# cc2_schematic.net
KiCad netlist of a schematic drawn in EasyEDA
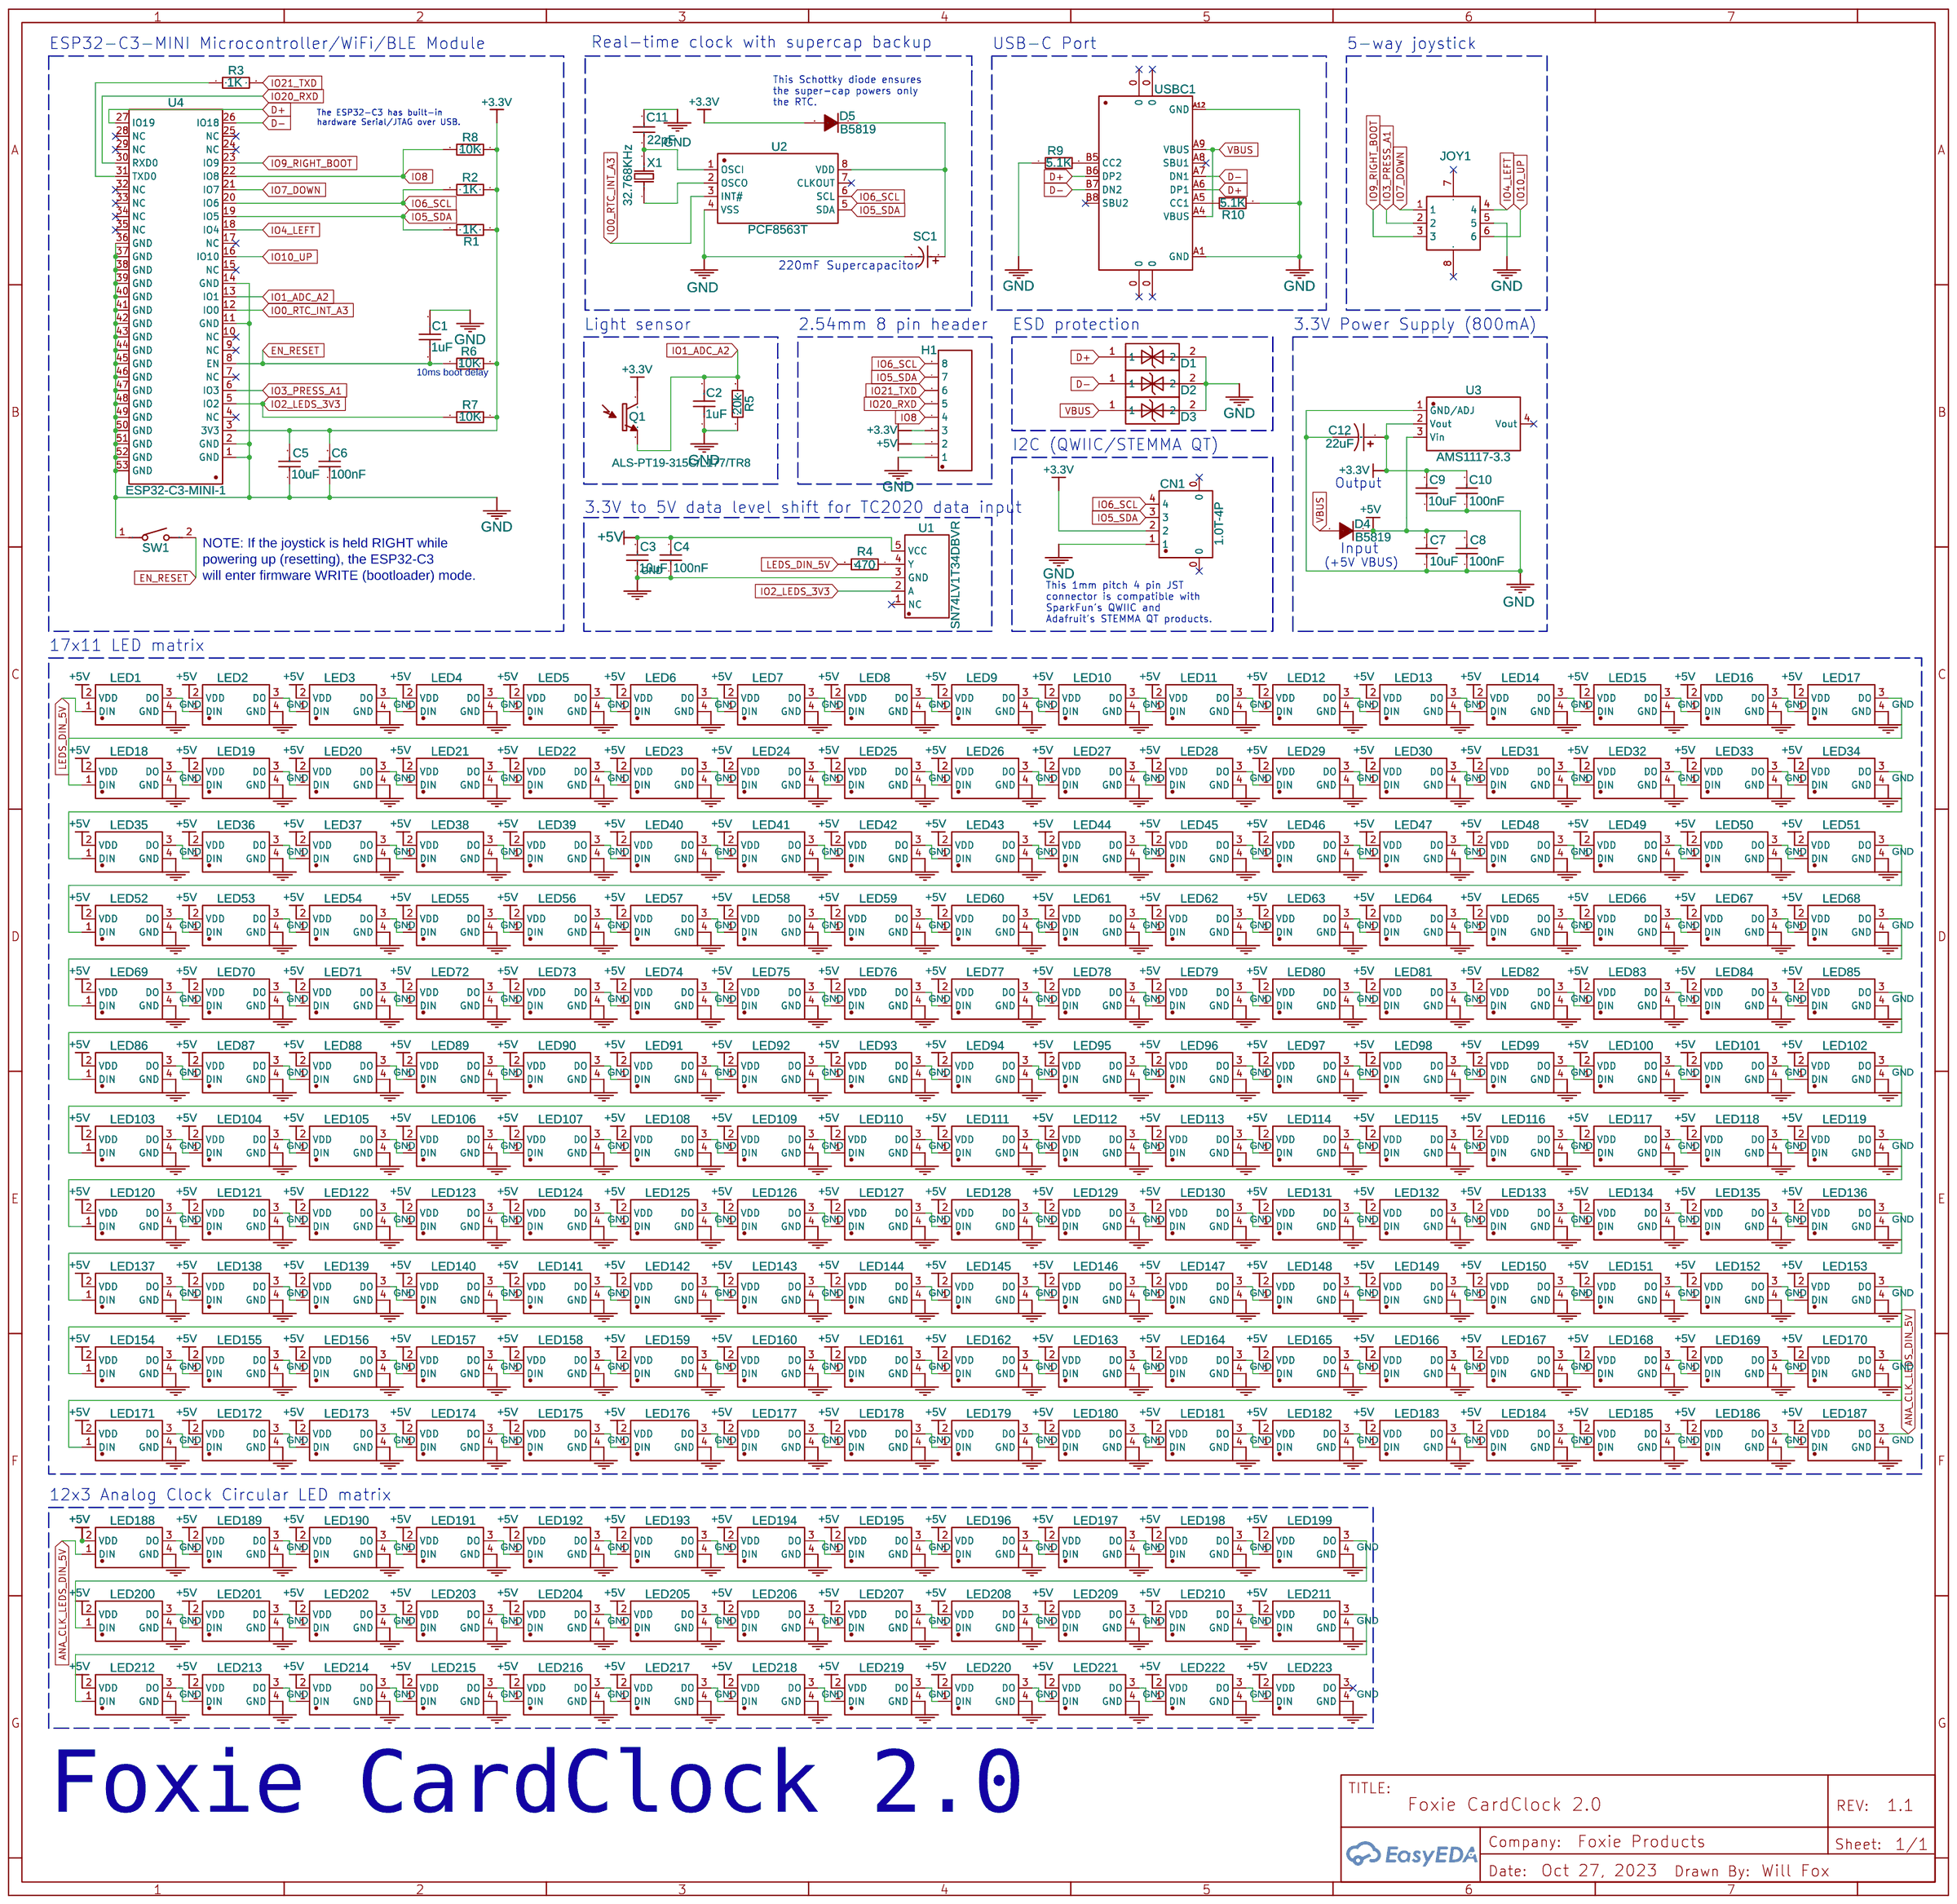
[diagram p0: schematic sheet]

(export (version "E")
  (design (tool "Eeschema 10.0.6"))
  (components
    (comp (ref "C1")
      (value "1uF")
      (fields (field (name "Manufacturer Part") "CL05A105KA5NQNC") (field (name "Manufacturer") "SAMSUNG"))
      (libsource (lib "") (part "CL05A105KA5NQNC"))
    )
    (comp (ref "C2")
      (value "1uF")
      (fields (field (name "Manufacturer Part") "CL05A105KA5NQNC") (field (name "Manufacturer") "SAMSUNG"))
      (libsource (lib "") (part "CL05A105KA5NQNC"))
    )
    (comp (ref "C3")
      (value "10uF")
      (fields (field (name "Manufacturer Part") "CL05A106MQ5NUNC") (field (name "Manufacturer") "SAMSUNG"))
      (libsource (lib "") (part "CL05A106MQ5NUNC"))
    )
    (comp (ref "C4")
      (value "100nF")
      (fields (field (name "Manufacturer Part") "CL05B104KO5NNNC") (field (name "Manufacturer") "SAMSUNG"))
      (libsource (lib "") (part "CL05B104KO5NNNC"))
    )
    (comp (ref "C5")
      (value "10uF")
      (fields (field (name "Manufacturer Part") "CL05A106MQ5NUNC") (field (name "Manufacturer") "SAMSUNG"))
      (libsource (lib "") (part "CL05A106MQ5NUNC"))
    )
    (comp (ref "C6")
      (value "100nF")
      (fields (field (name "Manufacturer Part") "CL05B104KO5NNNC") (field (name "Manufacturer") "SAMSUNG"))
      (libsource (lib "") (part "CL05B104KO5NNNC"))
    )
    (comp (ref "C7")
      (value "10uF")
      (fields (field (name "Manufacturer Part") "CL05A106MQ5NUNC") (field (name "Manufacturer") "SAMSUNG"))
      (libsource (lib "") (part "CL05A106MQ5NUNC"))
    )
    (comp (ref "C8")
      (value "100nF")
      (fields (field (name "Manufacturer Part") "CL05B104KO5NNNC") (field (name "Manufacturer") "SAMSUNG"))
      (libsource (lib "") (part "CL05B104KO5NNNC"))
    )
    (comp (ref "C9")
      (value "10uF")
      (fields (field (name "Manufacturer Part") "CL05A106MQ5NUNC") (field (name "Manufacturer") "SAMSUNG"))
      (libsource (lib "") (part "CL05A106MQ5NUNC"))
    )
    (comp (ref "C10")
      (value "100nF")
      (fields (field (name "Manufacturer Part") "CL05B104KO5NNNC") (field (name "Manufacturer") "SAMSUNG"))
      (libsource (lib "") (part "CL05B104KO5NNNC"))
    )
    (comp (ref "C11")
      (value "22pF")
      (fields (field (name "Manufacturer Part") "0402CG220J500NT") (field (name "Manufacturer") "FH"))
      (libsource (lib "") (part "0402CG220J500NT"))
    )
    (comp (ref "C12")
      (value "22uF")
      (fields (field (name "Manufacturer Part") "TC212A226K010Y") (field (name "Manufacturer") "Sunlord"))
      (libsource (lib "") (part "TC212A226K010Y"))
    )
    (comp (ref "CN1")
      (value "1.0T-4P")
      (fields (field (name "Manufacturer") "Boom Precision Elec"))
      (libsource (lib "") (part "1.0T-4P_C145956"))
    )
    (comp (ref "D1")
      (value "ULCE1005A015FR")
      (fields (field (name "Manufacturer") "ICT"))
      (libsource (lib "") (part "ULCE1005A015FR"))
    )
    (comp (ref "D2")
      (value "ULCE1005A015FR")
      (fields (field (name "Manufacturer") "ICT"))
      (libsource (lib "") (part "ULCE1005A015FR"))
    )
    (comp (ref "D3")
      (value "ULCE1005A015FR")
      (fields (field (name "Manufacturer") "ICT"))
      (libsource (lib "") (part "ULCE1005A015FR"))
    )
    (comp (ref "D4")
      (value "B5819")
      (fields (field (name "Manufacturer Part") "B5819W") (field (name "Manufacturer") "CJ"))
      (libsource (lib "") (part "B5819W_C8598"))
    )
    (comp (ref "D5")
      (value "B5819")
      (fields (field (name "Manufacturer Part") "B5819W") (field (name "Manufacturer") "CJ"))
      (libsource (lib "") (part "B5819W_C8598"))
    )
    (comp (ref "H1")
      (value "Header-Male-2.54_1x8")
      (fields
        (field (name "Manufacturer Part") "210S-1*8P L=11.6MMGold-plated black")
        (field (name "Manufacturer") "Ckmtw")
      )
      (libsource (lib "") (part "Header-Male-2.54_1x8"))
    )
    (comp (ref "JOY1")
      (value "K1-5202UA-02")
      (fields (field (name "Manufacturer") "HRO"))
      (libsource (lib "") (part "K1-5202UA-02"))
    )
    (comp (ref "LED1")
      (value "TC2020RGB-3CJH-TX1812Z5")
      (fields (field (name "Manufacturer") "TCWIN"))
      (libsource (lib "") (part "TC2020RGB-3CJH-TX1812Z5"))
    )
    (comp (ref "LED2")
      (value "TC2020RGB-3CJH-TX1812Z5")
      (fields (field (name "Manufacturer") "TCWIN"))
      (libsource (lib "") (part "TC2020RGB-3CJH-TX1812Z5"))
    )
    (comp (ref "LED3")
      (value "TC2020RGB-3CJH-TX1812Z5")
      (fields (field (name "Manufacturer") "TCWIN"))
      (libsource (lib "") (part "TC2020RGB-3CJH-TX1812Z5"))
    )
    (comp (ref "LED4")
      (value "TC2020RGB-3CJH-TX1812Z5")
      (fields (field (name "Manufacturer") "TCWIN"))
      (libsource (lib "") (part "TC2020RGB-3CJH-TX1812Z5"))
    )
    (comp (ref "LED5")
      (value "TC2020RGB-3CJH-TX1812Z5")
      (fields (field (name "Manufacturer") "TCWIN"))
      (libsource (lib "") (part "TC2020RGB-3CJH-TX1812Z5"))
    )
    (comp (ref "LED6")
      (value "TC2020RGB-3CJH-TX1812Z5")
      (fields (field (name "Manufacturer") "TCWIN"))
      (libsource (lib "") (part "TC2020RGB-3CJH-TX1812Z5"))
    )
    (comp (ref "LED7")
      (value "TC2020RGB-3CJH-TX1812Z5")
      (fields (field (name "Manufacturer") "TCWIN"))
      (libsource (lib "") (part "TC2020RGB-3CJH-TX1812Z5"))
    )
    (comp (ref "LED8")
      (value "TC2020RGB-3CJH-TX1812Z5")
      (fields (field (name "Manufacturer") "TCWIN"))
      (libsource (lib "") (part "TC2020RGB-3CJH-TX1812Z5"))
    )
    (comp (ref "LED9")
      (value "TC2020RGB-3CJH-TX1812Z5")
      (fields (field (name "Manufacturer") "TCWIN"))
      (libsource (lib "") (part "TC2020RGB-3CJH-TX1812Z5"))
    )
    (comp (ref "LED10")
      (value "TC2020RGB-3CJH-TX1812Z5")
      (fields (field (name "Manufacturer") "TCWIN"))
      (libsource (lib "") (part "TC2020RGB-3CJH-TX1812Z5"))
    )
    (comp (ref "LED11")
      (value "TC2020RGB-3CJH-TX1812Z5")
      (fields (field (name "Manufacturer") "TCWIN"))
      (libsource (lib "") (part "TC2020RGB-3CJH-TX1812Z5"))
    )
    (comp (ref "LED12")
      (value "TC2020RGB-3CJH-TX1812Z5")
      (fields (field (name "Manufacturer") "TCWIN"))
      (libsource (lib "") (part "TC2020RGB-3CJH-TX1812Z5"))
    )
    (comp (ref "LED13")
      (value "TC2020RGB-3CJH-TX1812Z5")
      (fields (field (name "Manufacturer") "TCWIN"))
      (libsource (lib "") (part "TC2020RGB-3CJH-TX1812Z5"))
    )
    (comp (ref "LED14")
      (value "TC2020RGB-3CJH-TX1812Z5")
      (fields (field (name "Manufacturer") "TCWIN"))
      (libsource (lib "") (part "TC2020RGB-3CJH-TX1812Z5"))
    )
    (comp (ref "LED15")
      (value "TC2020RGB-3CJH-TX1812Z5")
      (fields (field (name "Manufacturer") "TCWIN"))
      (libsource (lib "") (part "TC2020RGB-3CJH-TX1812Z5"))
    )
    (comp (ref "LED16")
      (value "TC2020RGB-3CJH-TX1812Z5")
      (fields (field (name "Manufacturer") "TCWIN"))
      (libsource (lib "") (part "TC2020RGB-3CJH-TX1812Z5"))
    )
    (comp (ref "LED17")
      (value "TC2020RGB-3CJH-TX1812Z5")
      (fields (field (name "Manufacturer") "TCWIN"))
      (libsource (lib "") (part "TC2020RGB-3CJH-TX1812Z5"))
    )
    (comp (ref "LED18")
      (value "TC2020RGB-3CJH-TX1812Z5")
      (fields (field (name "Manufacturer") "TCWIN"))
      (libsource (lib "") (part "TC2020RGB-3CJH-TX1812Z5"))
    )
    (comp (ref "LED19")
      (value "TC2020RGB-3CJH-TX1812Z5")
      (fields (field (name "Manufacturer") "TCWIN"))
      (libsource (lib "") (part "TC2020RGB-3CJH-TX1812Z5"))
    )
    (comp (ref "LED20")
      (value "TC2020RGB-3CJH-TX1812Z5")
      (fields (field (name "Manufacturer") "TCWIN"))
      (libsource (lib "") (part "TC2020RGB-3CJH-TX1812Z5"))
    )
    (comp (ref "LED21")
      (value "TC2020RGB-3CJH-TX1812Z5")
      (fields (field (name "Manufacturer") "TCWIN"))
      (libsource (lib "") (part "TC2020RGB-3CJH-TX1812Z5"))
    )
    (comp (ref "LED22")
      (value "TC2020RGB-3CJH-TX1812Z5")
      (fields (field (name "Manufacturer") "TCWIN"))
      (libsource (lib "") (part "TC2020RGB-3CJH-TX1812Z5"))
    )
    (comp (ref "LED23")
      (value "TC2020RGB-3CJH-TX1812Z5")
      (fields (field (name "Manufacturer") "TCWIN"))
      (libsource (lib "") (part "TC2020RGB-3CJH-TX1812Z5"))
    )
    (comp (ref "LED24")
      (value "TC2020RGB-3CJH-TX1812Z5")
      (fields (field (name "Manufacturer") "TCWIN"))
      (libsource (lib "") (part "TC2020RGB-3CJH-TX1812Z5"))
    )
    (comp (ref "LED25")
      (value "TC2020RGB-3CJH-TX1812Z5")
      (fields (field (name "Manufacturer") "TCWIN"))
      (libsource (lib "") (part "TC2020RGB-3CJH-TX1812Z5"))
    )
    (comp (ref "LED26")
      (value "TC2020RGB-3CJH-TX1812Z5")
      (fields (field (name "Manufacturer") "TCWIN"))
      (libsource (lib "") (part "TC2020RGB-3CJH-TX1812Z5"))
    )
    (comp (ref "LED27")
      (value "TC2020RGB-3CJH-TX1812Z5")
      (fields (field (name "Manufacturer") "TCWIN"))
      (libsource (lib "") (part "TC2020RGB-3CJH-TX1812Z5"))
    )
    (comp (ref "LED28")
      (value "TC2020RGB-3CJH-TX1812Z5")
      (fields (field (name "Manufacturer") "TCWIN"))
      (libsource (lib "") (part "TC2020RGB-3CJH-TX1812Z5"))
    )
    (comp (ref "LED29")
      (value "TC2020RGB-3CJH-TX1812Z5")
      (fields (field (name "Manufacturer") "TCWIN"))
      (libsource (lib "") (part "TC2020RGB-3CJH-TX1812Z5"))
    )
    (comp (ref "LED30")
      (value "TC2020RGB-3CJH-TX1812Z5")
      (fields (field (name "Manufacturer") "TCWIN"))
      (libsource (lib "") (part "TC2020RGB-3CJH-TX1812Z5"))
    )
    (comp (ref "LED31")
      (value "TC2020RGB-3CJH-TX1812Z5")
      (fields (field (name "Manufacturer") "TCWIN"))
      (libsource (lib "") (part "TC2020RGB-3CJH-TX1812Z5"))
    )
    (comp (ref "LED32")
      (value "TC2020RGB-3CJH-TX1812Z5")
      (fields (field (name "Manufacturer") "TCWIN"))
      (libsource (lib "") (part "TC2020RGB-3CJH-TX1812Z5"))
    )
    (comp (ref "LED33")
      (value "TC2020RGB-3CJH-TX1812Z5")
      (fields (field (name "Manufacturer") "TCWIN"))
      (libsource (lib "") (part "TC2020RGB-3CJH-TX1812Z5"))
    )
    (comp (ref "LED34")
      (value "TC2020RGB-3CJH-TX1812Z5")
      (fields (field (name "Manufacturer") "TCWIN"))
      (libsource (lib "") (part "TC2020RGB-3CJH-TX1812Z5"))
    )
    (comp (ref "LED35")
      (value "TC2020RGB-3CJH-TX1812Z5")
      (fields (field (name "Manufacturer") "TCWIN"))
      (libsource (lib "") (part "TC2020RGB-3CJH-TX1812Z5"))
    )
    (comp (ref "LED36")
      (value "TC2020RGB-3CJH-TX1812Z5")
      (fields (field (name "Manufacturer") "TCWIN"))
      (libsource (lib "") (part "TC2020RGB-3CJH-TX1812Z5"))
    )
    (comp (ref "LED37")
      (value "TC2020RGB-3CJH-TX1812Z5")
      (fields (field (name "Manufacturer") "TCWIN"))
      (libsource (lib "") (part "TC2020RGB-3CJH-TX1812Z5"))
    )
    (comp (ref "LED38")
      (value "TC2020RGB-3CJH-TX1812Z5")
      (fields (field (name "Manufacturer") "TCWIN"))
      (libsource (lib "") (part "TC2020RGB-3CJH-TX1812Z5"))
    )
    (comp (ref "LED39")
      (value "TC2020RGB-3CJH-TX1812Z5")
      (fields (field (name "Manufacturer") "TCWIN"))
      (libsource (lib "") (part "TC2020RGB-3CJH-TX1812Z5"))
    )
    (comp (ref "LED40")
      (value "TC2020RGB-3CJH-TX1812Z5")
      (fields (field (name "Manufacturer") "TCWIN"))
      (libsource (lib "") (part "TC2020RGB-3CJH-TX1812Z5"))
    )
    (comp (ref "LED41")
      (value "TC2020RGB-3CJH-TX1812Z5")
      (fields (field (name "Manufacturer") "TCWIN"))
      (libsource (lib "") (part "TC2020RGB-3CJH-TX1812Z5"))
    )
    (comp (ref "LED42")
      (value "TC2020RGB-3CJH-TX1812Z5")
      (fields (field (name "Manufacturer") "TCWIN"))
      (libsource (lib "") (part "TC2020RGB-3CJH-TX1812Z5"))
    )
    (comp (ref "LED43")
      (value "TC2020RGB-3CJH-TX1812Z5")
      (fields (field (name "Manufacturer") "TCWIN"))
      (libsource (lib "") (part "TC2020RGB-3CJH-TX1812Z5"))
    )
    (comp (ref "LED44")
      (value "TC2020RGB-3CJH-TX1812Z5")
      (fields (field (name "Manufacturer") "TCWIN"))
      (libsource (lib "") (part "TC2020RGB-3CJH-TX1812Z5"))
    )
    (comp (ref "LED45")
      (value "TC2020RGB-3CJH-TX1812Z5")
      (fields (field (name "Manufacturer") "TCWIN"))
      (libsource (lib "") (part "TC2020RGB-3CJH-TX1812Z5"))
    )
    (comp (ref "LED46")
      (value "TC2020RGB-3CJH-TX1812Z5")
      (fields (field (name "Manufacturer") "TCWIN"))
      (libsource (lib "") (part "TC2020RGB-3CJH-TX1812Z5"))
    )
    (comp (ref "LED47")
      (value "TC2020RGB-3CJH-TX1812Z5")
      (fields (field (name "Manufacturer") "TCWIN"))
      (libsource (lib "") (part "TC2020RGB-3CJH-TX1812Z5"))
    )
    (comp (ref "LED48")
      (value "TC2020RGB-3CJH-TX1812Z5")
      (fields (field (name "Manufacturer") "TCWIN"))
      (libsource (lib "") (part "TC2020RGB-3CJH-TX1812Z5"))
    )
    (comp (ref "LED49")
      (value "TC2020RGB-3CJH-TX1812Z5")
      (fields (field (name "Manufacturer") "TCWIN"))
      (libsource (lib "") (part "TC2020RGB-3CJH-TX1812Z5"))
    )
    (comp (ref "LED50")
      (value "TC2020RGB-3CJH-TX1812Z5")
      (fields (field (name "Manufacturer") "TCWIN"))
      (libsource (lib "") (part "TC2020RGB-3CJH-TX1812Z5"))
    )
    (comp (ref "LED51")
      (value "TC2020RGB-3CJH-TX1812Z5")
      (fields (field (name "Manufacturer") "TCWIN"))
      (libsource (lib "") (part "TC2020RGB-3CJH-TX1812Z5"))
    )
    (comp (ref "LED52")
      (value "TC2020RGB-3CJH-TX1812Z5")
      (fields (field (name "Manufacturer") "TCWIN"))
      (libsource (lib "") (part "TC2020RGB-3CJH-TX1812Z5"))
    )
    (comp (ref "LED53")
      (value "TC2020RGB-3CJH-TX1812Z5")
      (fields (field (name "Manufacturer") "TCWIN"))
      (libsource (lib "") (part "TC2020RGB-3CJH-TX1812Z5"))
    )
    (comp (ref "LED54")
      (value "TC2020RGB-3CJH-TX1812Z5")
      (fields (field (name "Manufacturer") "TCWIN"))
      (libsource (lib "") (part "TC2020RGB-3CJH-TX1812Z5"))
    )
    (comp (ref "LED55")
      (value "TC2020RGB-3CJH-TX1812Z5")
      (fields (field (name "Manufacturer") "TCWIN"))
      (libsource (lib "") (part "TC2020RGB-3CJH-TX1812Z5"))
    )
    (comp (ref "LED56")
      (value "TC2020RGB-3CJH-TX1812Z5")
      (fields (field (name "Manufacturer") "TCWIN"))
      (libsource (lib "") (part "TC2020RGB-3CJH-TX1812Z5"))
    )
    (comp (ref "LED57")
      (value "TC2020RGB-3CJH-TX1812Z5")
      (fields (field (name "Manufacturer") "TCWIN"))
      (libsource (lib "") (part "TC2020RGB-3CJH-TX1812Z5"))
    )
    (comp (ref "LED58")
      (value "TC2020RGB-3CJH-TX1812Z5")
      (fields (field (name "Manufacturer") "TCWIN"))
      (libsource (lib "") (part "TC2020RGB-3CJH-TX1812Z5"))
    )
    (comp (ref "LED59")
      (value "TC2020RGB-3CJH-TX1812Z5")
      (fields (field (name "Manufacturer") "TCWIN"))
      (libsource (lib "") (part "TC2020RGB-3CJH-TX1812Z5"))
    )
    (comp (ref "LED60")
      (value "TC2020RGB-3CJH-TX1812Z5")
      (fields (field (name "Manufacturer") "TCWIN"))
      (libsource (lib "") (part "TC2020RGB-3CJH-TX1812Z5"))
    )
    (comp (ref "LED61")
      (value "TC2020RGB-3CJH-TX1812Z5")
      (fields (field (name "Manufacturer") "TCWIN"))
      (libsource (lib "") (part "TC2020RGB-3CJH-TX1812Z5"))
    )
    (comp (ref "LED62")
      (value "TC2020RGB-3CJH-TX1812Z5")
      (fields (field (name "Manufacturer") "TCWIN"))
      (libsource (lib "") (part "TC2020RGB-3CJH-TX1812Z5"))
    )
    (comp (ref "LED63")
      (value "TC2020RGB-3CJH-TX1812Z5")
      (fields (field (name "Manufacturer") "TCWIN"))
      (libsource (lib "") (part "TC2020RGB-3CJH-TX1812Z5"))
    )
    (comp (ref "LED64")
      (value "TC2020RGB-3CJH-TX1812Z5")
      (fields (field (name "Manufacturer") "TCWIN"))
      (libsource (lib "") (part "TC2020RGB-3CJH-TX1812Z5"))
    )
    (comp (ref "LED65")
      (value "TC2020RGB-3CJH-TX1812Z5")
      (fields (field (name "Manufacturer") "TCWIN"))
      (libsource (lib "") (part "TC2020RGB-3CJH-TX1812Z5"))
    )
    (comp (ref "LED66")
      (value "TC2020RGB-3CJH-TX1812Z5")
      (fields (field (name "Manufacturer") "TCWIN"))
      (libsource (lib "") (part "TC2020RGB-3CJH-TX1812Z5"))
    )
    (comp (ref "LED67")
      (value "TC2020RGB-3CJH-TX1812Z5")
      (fields (field (name "Manufacturer") "TCWIN"))
      (libsource (lib "") (part "TC2020RGB-3CJH-TX1812Z5"))
    )
    (comp (ref "LED68")
      (value "TC2020RGB-3CJH-TX1812Z5")
      (fields (field (name "Manufacturer") "TCWIN"))
      (libsource (lib "") (part "TC2020RGB-3CJH-TX1812Z5"))
    )
    (comp (ref "LED69")
      (value "TC2020RGB-3CJH-TX1812Z5")
      (fields (field (name "Manufacturer") "TCWIN"))
      (libsource (lib "") (part "TC2020RGB-3CJH-TX1812Z5"))
    )
    (comp (ref "LED70")
      (value "TC2020RGB-3CJH-TX1812Z5")
      (fields (field (name "Manufacturer") "TCWIN"))
      (libsource (lib "") (part "TC2020RGB-3CJH-TX1812Z5"))
    )
    (comp (ref "LED71")
      (value "TC2020RGB-3CJH-TX1812Z5")
      (fields (field (name "Manufacturer") "TCWIN"))
      (libsource (lib "") (part "TC2020RGB-3CJH-TX1812Z5"))
    )
    (comp (ref "LED72")
      (value "TC2020RGB-3CJH-TX1812Z5")
      (fields (field (name "Manufacturer") "TCWIN"))
      (libsource (lib "") (part "TC2020RGB-3CJH-TX1812Z5"))
    )
    (comp (ref "LED73")
      (value "TC2020RGB-3CJH-TX1812Z5")
      (fields (field (name "Manufacturer") "TCWIN"))
      (libsource (lib "") (part "TC2020RGB-3CJH-TX1812Z5"))
    )
    (comp (ref "LED74")
      (value "TC2020RGB-3CJH-TX1812Z5")
      (fields (field (name "Manufacturer") "TCWIN"))
      (libsource (lib "") (part "TC2020RGB-3CJH-TX1812Z5"))
    )
    (comp (ref "LED75")
      (value "TC2020RGB-3CJH-TX1812Z5")
      (fields (field (name "Manufacturer") "TCWIN"))
      (libsource (lib "") (part "TC2020RGB-3CJH-TX1812Z5"))
    )
    (comp (ref "LED76")
      (value "TC2020RGB-3CJH-TX1812Z5")
      (fields (field (name "Manufacturer") "TCWIN"))
      (libsource (lib "") (part "TC2020RGB-3CJH-TX1812Z5"))
    )
    (comp (ref "LED77")
      (value "TC2020RGB-3CJH-TX1812Z5")
      (fields (field (name "Manufacturer") "TCWIN"))
      (libsource (lib "") (part "TC2020RGB-3CJH-TX1812Z5"))
    )
    (comp (ref "LED78")
      (value "TC2020RGB-3CJH-TX1812Z5")
      (fields (field (name "Manufacturer") "TCWIN"))
      (libsource (lib "") (part "TC2020RGB-3CJH-TX1812Z5"))
    )
    (comp (ref "LED79")
      (value "TC2020RGB-3CJH-TX1812Z5")
      (fields (field (name "Manufacturer") "TCWIN"))
      (libsource (lib "") (part "TC2020RGB-3CJH-TX1812Z5"))
    )
    (comp (ref "LED80")
      (value "TC2020RGB-3CJH-TX1812Z5")
      (fields (field (name "Manufacturer") "TCWIN"))
      (libsource (lib "") (part "TC2020RGB-3CJH-TX1812Z5"))
    )
    (comp (ref "LED81")
      (value "TC2020RGB-3CJH-TX1812Z5")
      (fields (field (name "Manufacturer") "TCWIN"))
      (libsource (lib "") (part "TC2020RGB-3CJH-TX1812Z5"))
    )
    (comp (ref "LED82")
      (value "TC2020RGB-3CJH-TX1812Z5")
      (fields (field (name "Manufacturer") "TCWIN"))
      (libsource (lib "") (part "TC2020RGB-3CJH-TX1812Z5"))
    )
    (comp (ref "LED83")
      (value "TC2020RGB-3CJH-TX1812Z5")
      (fields (field (name "Manufacturer") "TCWIN"))
      (libsource (lib "") (part "TC2020RGB-3CJH-TX1812Z5"))
    )
    (comp (ref "LED84")
      (value "TC2020RGB-3CJH-TX1812Z5")
      (fields (field (name "Manufacturer") "TCWIN"))
      (libsource (lib "") (part "TC2020RGB-3CJH-TX1812Z5"))
    )
    (comp (ref "LED85")
      (value "TC2020RGB-3CJH-TX1812Z5")
      (fields (field (name "Manufacturer") "TCWIN"))
      (libsource (lib "") (part "TC2020RGB-3CJH-TX1812Z5"))
    )
    (comp (ref "LED86")
      (value "TC2020RGB-3CJH-TX1812Z5")
      (fields (field (name "Manufacturer") "TCWIN"))
      (libsource (lib "") (part "TC2020RGB-3CJH-TX1812Z5"))
    )
    (comp (ref "LED87")
      (value "TC2020RGB-3CJH-TX1812Z5")
      (fields (field (name "Manufacturer") "TCWIN"))
      (libsource (lib "") (part "TC2020RGB-3CJH-TX1812Z5"))
    )
    (comp (ref "LED88")
      (value "TC2020RGB-3CJH-TX1812Z5")
      (fields (field (name "Manufacturer") "TCWIN"))
      (libsource (lib "") (part "TC2020RGB-3CJH-TX1812Z5"))
    )
    (comp (ref "LED89")
      (value "TC2020RGB-3CJH-TX1812Z5")
      (fields (field (name "Manufacturer") "TCWIN"))
      (libsource (lib "") (part "TC2020RGB-3CJH-TX1812Z5"))
    )
    (comp (ref "LED90")
      (value "TC2020RGB-3CJH-TX1812Z5")
      (fields (field (name "Manufacturer") "TCWIN"))
      (libsource (lib "") (part "TC2020RGB-3CJH-TX1812Z5"))
    )
    (comp (ref "LED91")
      (value "TC2020RGB-3CJH-TX1812Z5")
      (fields (field (name "Manufacturer") "TCWIN"))
      (libsource (lib "") (part "TC2020RGB-3CJH-TX1812Z5"))
    )
    (comp (ref "LED92")
      (value "TC2020RGB-3CJH-TX1812Z5")
      (fields (field (name "Manufacturer") "TCWIN"))
      (libsource (lib "") (part "TC2020RGB-3CJH-TX1812Z5"))
    )
    (comp (ref "LED93")
      (value "TC2020RGB-3CJH-TX1812Z5")
      (fields (field (name "Manufacturer") "TCWIN"))
      (libsource (lib "") (part "TC2020RGB-3CJH-TX1812Z5"))
    )
    (comp (ref "LED94")
      (value "TC2020RGB-3CJH-TX1812Z5")
      (fields (field (name "Manufacturer") "TCWIN"))
      (libsource (lib "") (part "TC2020RGB-3CJH-TX1812Z5"))
    )
    (comp (ref "LED95")
      (value "TC2020RGB-3CJH-TX1812Z5")
      (fields (field (name "Manufacturer") "TCWIN"))
      (libsource (lib "") (part "TC2020RGB-3CJH-TX1812Z5"))
    )
    (comp (ref "LED96")
      (value "TC2020RGB-3CJH-TX1812Z5")
      (fields (field (name "Manufacturer") "TCWIN"))
      (libsource (lib "") (part "TC2020RGB-3CJH-TX1812Z5"))
    )
    (comp (ref "LED97")
      (value "TC2020RGB-3CJH-TX1812Z5")
      (fields (field (name "Manufacturer") "TCWIN"))
      (libsource (lib "") (part "TC2020RGB-3CJH-TX1812Z5"))
    )
    (comp (ref "LED98")
      (value "TC2020RGB-3CJH-TX1812Z5")
      (fields (field (name "Manufacturer") "TCWIN"))
      (libsource (lib "") (part "TC2020RGB-3CJH-TX1812Z5"))
    )
    (comp (ref "LED99")
      (value "TC2020RGB-3CJH-TX1812Z5")
      (fields (field (name "Manufacturer") "TCWIN"))
      (libsource (lib "") (part "TC2020RGB-3CJH-TX1812Z5"))
    )
    (comp (ref "LED100")
      (value "TC2020RGB-3CJH-TX1812Z5")
      (fields (field (name "Manufacturer") "TCWIN"))
      (libsource (lib "") (part "TC2020RGB-3CJH-TX1812Z5"))
    )
    (comp (ref "LED101")
      (value "TC2020RGB-3CJH-TX1812Z5")
      (fields (field (name "Manufacturer") "TCWIN"))
      (libsource (lib "") (part "TC2020RGB-3CJH-TX1812Z5"))
    )
    (comp (ref "LED102")
      (value "TC2020RGB-3CJH-TX1812Z5")
      (fields (field (name "Manufacturer") "TCWIN"))
      (libsource (lib "") (part "TC2020RGB-3CJH-TX1812Z5"))
    )
    (comp (ref "LED103")
      (value "TC2020RGB-3CJH-TX1812Z5")
      (fields (field (name "Manufacturer") "TCWIN"))
      (libsource (lib "") (part "TC2020RGB-3CJH-TX1812Z5"))
    )
    (comp (ref "LED104")
      (value "TC2020RGB-3CJH-TX1812Z5")
      (fields (field (name "Manufacturer") "TCWIN"))
      (libsource (lib "") (part "TC2020RGB-3CJH-TX1812Z5"))
    )
    (comp (ref "LED105")
      (value "TC2020RGB-3CJH-TX1812Z5")
      (fields (field (name "Manufacturer") "TCWIN"))
      (libsource (lib "") (part "TC2020RGB-3CJH-TX1812Z5"))
    )
    (comp (ref "LED106")
      (value "TC2020RGB-3CJH-TX1812Z5")
      (fields (field (name "Manufacturer") "TCWIN"))
      (libsource (lib "") (part "TC2020RGB-3CJH-TX1812Z5"))
    )
    (comp (ref "LED107")
      (value "TC2020RGB-3CJH-TX1812Z5")
      (fields (field (name "Manufacturer") "TCWIN"))
      (libsource (lib "") (part "TC2020RGB-3CJH-TX1812Z5"))
    )
    (comp (ref "LED108")
      (value "TC2020RGB-3CJH-TX1812Z5")
      (fields (field (name "Manufacturer") "TCWIN"))
      (libsource (lib "") (part "TC2020RGB-3CJH-TX1812Z5"))
    )
    (comp (ref "LED109")
      (value "TC2020RGB-3CJH-TX1812Z5")
      (fields (field (name "Manufacturer") "TCWIN"))
      (libsource (lib "") (part "TC2020RGB-3CJH-TX1812Z5"))
    )
    (comp (ref "LED110")
      (value "TC2020RGB-3CJH-TX1812Z5")
      (fields (field (name "Manufacturer") "TCWIN"))
      (libsource (lib "") (part "TC2020RGB-3CJH-TX1812Z5"))
    )
    (comp (ref "LED111")
      (value "TC2020RGB-3CJH-TX1812Z5")
      (fields (field (name "Manufacturer") "TCWIN"))
      (libsource (lib "") (part "TC2020RGB-3CJH-TX1812Z5"))
    )
    (comp (ref "LED112")
      (value "TC2020RGB-3CJH-TX1812Z5")
      (fields (field (name "Manufacturer") "TCWIN"))
      (libsource (lib "") (part "TC2020RGB-3CJH-TX1812Z5"))
    )
    (comp (ref "LED113")
      (value "TC2020RGB-3CJH-TX1812Z5")
      (fields (field (name "Manufacturer") "TCWIN"))
      (libsource (lib "") (part "TC2020RGB-3CJH-TX1812Z5"))
    )
    (comp (ref "LED114")
      (value "TC2020RGB-3CJH-TX1812Z5")
      (fields (field (name "Manufacturer") "TCWIN"))
      (libsource (lib "") (part "TC2020RGB-3CJH-TX1812Z5"))
    )
    (comp (ref "LED115")
      (value "TC2020RGB-3CJH-TX1812Z5")
      (fields (field (name "Manufacturer") "TCWIN"))
      (libsource (lib "") (part "TC2020RGB-3CJH-TX1812Z5"))
    )
    (comp (ref "LED116")
      (value "TC2020RGB-3CJH-TX1812Z5")
      (fields (field (name "Manufacturer") "TCWIN"))
      (libsource (lib "") (part "TC2020RGB-3CJH-TX1812Z5"))
    )
    (comp (ref "LED117")
      (value "TC2020RGB-3CJH-TX1812Z5")
      (fields (field (name "Manufacturer") "TCWIN"))
      (libsource (lib "") (part "TC2020RGB-3CJH-TX1812Z5"))
    )
    (comp (ref "LED118")
      (value "TC2020RGB-3CJH-TX1812Z5")
      (fields (field (name "Manufacturer") "TCWIN"))
      (libsource (lib "") (part "TC2020RGB-3CJH-TX1812Z5"))
    )
    (comp (ref "LED119")
      (value "TC2020RGB-3CJH-TX1812Z5")
      (fields (field (name "Manufacturer") "TCWIN"))
      (libsource (lib "") (part "TC2020RGB-3CJH-TX1812Z5"))
    )
    (comp (ref "LED120")
      (value "TC2020RGB-3CJH-TX1812Z5")
      (fields (field (name "Manufacturer") "TCWIN"))
      (libsource (lib "") (part "TC2020RGB-3CJH-TX1812Z5"))
    )
    (comp (ref "LED121")
      (value "TC2020RGB-3CJH-TX1812Z5")
      (fields (field (name "Manufacturer") "TCWIN"))
      (libsource (lib "") (part "TC2020RGB-3CJH-TX1812Z5"))
    )
    (comp (ref "LED122")
      (value "TC2020RGB-3CJH-TX1812Z5")
      (fields (field (name "Manufacturer") "TCWIN"))
      (libsource (lib "") (part "TC2020RGB-3CJH-TX1812Z5"))
    )
    (comp (ref "LED123")
      (value "TC2020RGB-3CJH-TX1812Z5")
      (fields (field (name "Manufacturer") "TCWIN"))
      (libsource (lib "") (part "TC2020RGB-3CJH-TX1812Z5"))
    )
    (comp (ref "LED124")
      (value "TC2020RGB-3CJH-TX1812Z5")
      (fields (field (name "Manufacturer") "TCWIN"))
      (libsource (lib "") (part "TC2020RGB-3CJH-TX1812Z5"))
    )
    (comp (ref "LED125")
      (value "TC2020RGB-3CJH-TX1812Z5")
      (fields (field (name "Manufacturer") "TCWIN"))
      (libsource (lib "") (part "TC2020RGB-3CJH-TX1812Z5"))
    )
    (comp (ref "LED126")
      (value "TC2020RGB-3CJH-TX1812Z5")
      (fields (field (name "Manufacturer") "TCWIN"))
      (libsource (lib "") (part "TC2020RGB-3CJH-TX1812Z5"))
    )
    (comp (ref "LED127")
      (value "TC2020RGB-3CJH-TX1812Z5")
      (fields (field (name "Manufacturer") "TCWIN"))
      (libsource (lib "") (part "TC2020RGB-3CJH-TX1812Z5"))
    )
    (comp (ref "LED128")
      (value "TC2020RGB-3CJH-TX1812Z5")
      (fields (field (name "Manufacturer") "TCWIN"))
      (libsource (lib "") (part "TC2020RGB-3CJH-TX1812Z5"))
    )
    (comp (ref "LED129")
      (value "TC2020RGB-3CJH-TX1812Z5")
      (fields (field (name "Manufacturer") "TCWIN"))
      (libsource (lib "") (part "TC2020RGB-3CJH-TX1812Z5"))
    )
    (comp (ref "LED130")
      (value "TC2020RGB-3CJH-TX1812Z5")
      (fields (field (name "Manufacturer") "TCWIN"))
      (libsource (lib "") (part "TC2020RGB-3CJH-TX1812Z5"))
    )
    (comp (ref "LED131")
      (value "TC2020RGB-3CJH-TX1812Z5")
      (fields (field (name "Manufacturer") "TCWIN"))
      (libsource (lib "") (part "TC2020RGB-3CJH-TX1812Z5"))
    )
    (comp (ref "LED132")
      (value "TC2020RGB-3CJH-TX1812Z5")
      (fields (field (name "Manufacturer") "TCWIN"))
      (libsource (lib "") (part "TC2020RGB-3CJH-TX1812Z5"))
    )
    (comp (ref "LED133")
      (value "TC2020RGB-3CJH-TX1812Z5")
      (fields (field (name "Manufacturer") "TCWIN"))
      (libsource (lib "") (part "TC2020RGB-3CJH-TX1812Z5"))
    )
    (comp (ref "LED134")
      (value "TC2020RGB-3CJH-TX1812Z5")
      (fields (field (name "Manufacturer") "TCWIN"))
      (libsource (lib "") (part "TC2020RGB-3CJH-TX1812Z5"))
    )
    (comp (ref "LED135")
      (value "TC2020RGB-3CJH-TX1812Z5")
      (fields (field (name "Manufacturer") "TCWIN"))
      (libsource (lib "") (part "TC2020RGB-3CJH-TX1812Z5"))
    )
    (comp (ref "LED136")
      (value "TC2020RGB-3CJH-TX1812Z5")
      (fields (field (name "Manufacturer") "TCWIN"))
      (libsource (lib "") (part "TC2020RGB-3CJH-TX1812Z5"))
    )
    (comp (ref "LED137")
      (value "TC2020RGB-3CJH-TX1812Z5")
      (fields (field (name "Manufacturer") "TCWIN"))
      (libsource (lib "") (part "TC2020RGB-3CJH-TX1812Z5"))
    )
    (comp (ref "LED138")
      (value "TC2020RGB-3CJH-TX1812Z5")
      (fields (field (name "Manufacturer") "TCWIN"))
      (libsource (lib "") (part "TC2020RGB-3CJH-TX1812Z5"))
    )
    (comp (ref "LED139")
      (value "TC2020RGB-3CJH-TX1812Z5")
      (fields (field (name "Manufacturer") "TCWIN"))
      (libsource (lib "") (part "TC2020RGB-3CJH-TX1812Z5"))
    )
    (comp (ref "LED140")
      (value "TC2020RGB-3CJH-TX1812Z5")
      (fields (field (name "Manufacturer") "TCWIN"))
      (libsource (lib "") (part "TC2020RGB-3CJH-TX1812Z5"))
    )
    (comp (ref "LED141")
      (value "TC2020RGB-3CJH-TX1812Z5")
      (fields (field (name "Manufacturer") "TCWIN"))
      (libsource (lib "") (part "TC2020RGB-3CJH-TX1812Z5"))
    )
    (comp (ref "LED142")
      (value "TC2020RGB-3CJH-TX1812Z5")
      (fields (field (name "Manufacturer") "TCWIN"))
      (libsource (lib "") (part "TC2020RGB-3CJH-TX1812Z5"))
    )
    (comp (ref "LED143")
      (value "TC2020RGB-3CJH-TX1812Z5")
      (fields (field (name "Manufacturer") "TCWIN"))
      (libsource (lib "") (part "TC2020RGB-3CJH-TX1812Z5"))
    )
    (comp (ref "LED144")
      (value "TC2020RGB-3CJH-TX1812Z5")
      (fields (field (name "Manufacturer") "TCWIN"))
      (libsource (lib "") (part "TC2020RGB-3CJH-TX1812Z5"))
    )
    (comp (ref "LED145")
      (value "TC2020RGB-3CJH-TX1812Z5")
      (fields (field (name "Manufacturer") "TCWIN"))
      (libsource (lib "") (part "TC2020RGB-3CJH-TX1812Z5"))
    )
    (comp (ref "LED146")
      (value "TC2020RGB-3CJH-TX1812Z5")
      (fields (field (name "Manufacturer") "TCWIN"))
      (libsource (lib "") (part "TC2020RGB-3CJH-TX1812Z5"))
    )
    (comp (ref "LED147")
      (value "TC2020RGB-3CJH-TX1812Z5")
      (fields (field (name "Manufacturer") "TCWIN"))
      (libsource (lib "") (part "TC2020RGB-3CJH-TX1812Z5"))
    )
    (comp (ref "LED148")
      (value "TC2020RGB-3CJH-TX1812Z5")
      (fields (field (name "Manufacturer") "TCWIN"))
      (libsource (lib "") (part "TC2020RGB-3CJH-TX1812Z5"))
    )
    (comp (ref "LED149")
      (value "TC2020RGB-3CJH-TX1812Z5")
      (fields (field (name "Manufacturer") "TCWIN"))
      (libsource (lib "") (part "TC2020RGB-3CJH-TX1812Z5"))
    )
    (comp (ref "LED150")
      (value "TC2020RGB-3CJH-TX1812Z5")
      (fields (field (name "Manufacturer") "TCWIN"))
      (libsource (lib "") (part "TC2020RGB-3CJH-TX1812Z5"))
    )
    (comp (ref "LED151")
      (value "TC2020RGB-3CJH-TX1812Z5")
      (fields (field (name "Manufacturer") "TCWIN"))
      (libsource (lib "") (part "TC2020RGB-3CJH-TX1812Z5"))
    )
    (comp (ref "LED152")
      (value "TC2020RGB-3CJH-TX1812Z5")
      (fields (field (name "Manufacturer") "TCWIN"))
      (libsource (lib "") (part "TC2020RGB-3CJH-TX1812Z5"))
    )
    (comp (ref "LED153")
      (value "TC2020RGB-3CJH-TX1812Z5")
      (fields (field (name "Manufacturer") "TCWIN"))
      (libsource (lib "") (part "TC2020RGB-3CJH-TX1812Z5"))
    )
    (comp (ref "LED154")
      (value "TC2020RGB-3CJH-TX1812Z5")
      (fields (field (name "Manufacturer") "TCWIN"))
      (libsource (lib "") (part "TC2020RGB-3CJH-TX1812Z5"))
    )
    (comp (ref "LED155")
      (value "TC2020RGB-3CJH-TX1812Z5")
      (fields (field (name "Manufacturer") "TCWIN"))
      (libsource (lib "") (part "TC2020RGB-3CJH-TX1812Z5"))
    )
    (comp (ref "LED156")
      (value "TC2020RGB-3CJH-TX1812Z5")
      (fields (field (name "Manufacturer") "TCWIN"))
      (libsource (lib "") (part "TC2020RGB-3CJH-TX1812Z5"))
    )
    (comp (ref "LED157")
      (value "TC2020RGB-3CJH-TX1812Z5")
      (fields (field (name "Manufacturer") "TCWIN"))
      (libsource (lib "") (part "TC2020RGB-3CJH-TX1812Z5"))
    )
    (comp (ref "LED158")
      (value "TC2020RGB-3CJH-TX1812Z5")
      (fields (field (name "Manufacturer") "TCWIN"))
      (libsource (lib "") (part "TC2020RGB-3CJH-TX1812Z5"))
    )
    (comp (ref "LED159")
      (value "TC2020RGB-3CJH-TX1812Z5")
      (fields (field (name "Manufacturer") "TCWIN"))
      (libsource (lib "") (part "TC2020RGB-3CJH-TX1812Z5"))
    )
    (comp (ref "LED160")
      (value "TC2020RGB-3CJH-TX1812Z5")
      (fields (field (name "Manufacturer") "TCWIN"))
      (libsource (lib "") (part "TC2020RGB-3CJH-TX1812Z5"))
    )
    (comp (ref "LED161")
      (value "TC2020RGB-3CJH-TX1812Z5")
      (fields (field (name "Manufacturer") "TCWIN"))
      (libsource (lib "") (part "TC2020RGB-3CJH-TX1812Z5"))
    )
    (comp (ref "LED162")
      (value "TC2020RGB-3CJH-TX1812Z5")
      (fields (field (name "Manufacturer") "TCWIN"))
      (libsource (lib "") (part "TC2020RGB-3CJH-TX1812Z5"))
    )
    (comp (ref "LED163")
      (value "TC2020RGB-3CJH-TX1812Z5")
      (fields (field (name "Manufacturer") "TCWIN"))
      (libsource (lib "") (part "TC2020RGB-3CJH-TX1812Z5"))
    )
    (comp (ref "LED164")
      (value "TC2020RGB-3CJH-TX1812Z5")
      (fields (field (name "Manufacturer") "TCWIN"))
      (libsource (lib "") (part "TC2020RGB-3CJH-TX1812Z5"))
    )
    (comp (ref "LED165")
      (value "TC2020RGB-3CJH-TX1812Z5")
      (fields (field (name "Manufacturer") "TCWIN"))
      (libsource (lib "") (part "TC2020RGB-3CJH-TX1812Z5"))
    )
    (comp (ref "LED166")
      (value "TC2020RGB-3CJH-TX1812Z5")
      (fields (field (name "Manufacturer") "TCWIN"))
      (libsource (lib "") (part "TC2020RGB-3CJH-TX1812Z5"))
    )
    (comp (ref "LED167")
      (value "TC2020RGB-3CJH-TX1812Z5")
      (fields (field (name "Manufacturer") "TCWIN"))
      (libsource (lib "") (part "TC2020RGB-3CJH-TX1812Z5"))
    )
    (comp (ref "LED168")
      (value "TC2020RGB-3CJH-TX1812Z5")
      (fields (field (name "Manufacturer") "TCWIN"))
      (libsource (lib "") (part "TC2020RGB-3CJH-TX1812Z5"))
    )
    (comp (ref "LED169")
      (value "TC2020RGB-3CJH-TX1812Z5")
      (fields (field (name "Manufacturer") "TCWIN"))
      (libsource (lib "") (part "TC2020RGB-3CJH-TX1812Z5"))
    )
    (comp (ref "LED170")
      (value "TC2020RGB-3CJH-TX1812Z5")
      (fields (field (name "Manufacturer") "TCWIN"))
      (libsource (lib "") (part "TC2020RGB-3CJH-TX1812Z5"))
    )
    (comp (ref "LED171")
      (value "TC2020RGB-3CJH-TX1812Z5")
      (fields (field (name "Manufacturer") "TCWIN"))
      (libsource (lib "") (part "TC2020RGB-3CJH-TX1812Z5"))
    )
    (comp (ref "LED172")
      (value "TC2020RGB-3CJH-TX1812Z5")
      (fields (field (name "Manufacturer") "TCWIN"))
      (libsource (lib "") (part "TC2020RGB-3CJH-TX1812Z5"))
    )
    (comp (ref "LED173")
      (value "TC2020RGB-3CJH-TX1812Z5")
      (fields (field (name "Manufacturer") "TCWIN"))
      (libsource (lib "") (part "TC2020RGB-3CJH-TX1812Z5"))
    )
    (comp (ref "LED174")
      (value "TC2020RGB-3CJH-TX1812Z5")
      (fields (field (name "Manufacturer") "TCWIN"))
      (libsource (lib "") (part "TC2020RGB-3CJH-TX1812Z5"))
    )
    (comp (ref "LED175")
      (value "TC2020RGB-3CJH-TX1812Z5")
      (fields (field (name "Manufacturer") "TCWIN"))
      (libsource (lib "") (part "TC2020RGB-3CJH-TX1812Z5"))
    )
    (comp (ref "LED176")
      (value "TC2020RGB-3CJH-TX1812Z5")
      (fields (field (name "Manufacturer") "TCWIN"))
      (libsource (lib "") (part "TC2020RGB-3CJH-TX1812Z5"))
    )
    (comp (ref "LED177")
      (value "TC2020RGB-3CJH-TX1812Z5")
      (fields (field (name "Manufacturer") "TCWIN"))
      (libsource (lib "") (part "TC2020RGB-3CJH-TX1812Z5"))
    )
    (comp (ref "LED178")
      (value "TC2020RGB-3CJH-TX1812Z5")
      (fields (field (name "Manufacturer") "TCWIN"))
      (libsource (lib "") (part "TC2020RGB-3CJH-TX1812Z5"))
    )
    (comp (ref "LED179")
      (value "TC2020RGB-3CJH-TX1812Z5")
      (fields (field (name "Manufacturer") "TCWIN"))
      (libsource (lib "") (part "TC2020RGB-3CJH-TX1812Z5"))
    )
    (comp (ref "LED180")
      (value "TC2020RGB-3CJH-TX1812Z5")
      (fields (field (name "Manufacturer") "TCWIN"))
      (libsource (lib "") (part "TC2020RGB-3CJH-TX1812Z5"))
    )
    (comp (ref "LED181")
      (value "TC2020RGB-3CJH-TX1812Z5")
      (fields (field (name "Manufacturer") "TCWIN"))
      (libsource (lib "") (part "TC2020RGB-3CJH-TX1812Z5"))
    )
    (comp (ref "LED182")
      (value "TC2020RGB-3CJH-TX1812Z5")
      (fields (field (name "Manufacturer") "TCWIN"))
      (libsource (lib "") (part "TC2020RGB-3CJH-TX1812Z5"))
    )
    (comp (ref "LED183")
      (value "TC2020RGB-3CJH-TX1812Z5")
      (fields (field (name "Manufacturer") "TCWIN"))
      (libsource (lib "") (part "TC2020RGB-3CJH-TX1812Z5"))
    )
    (comp (ref "LED184")
      (value "TC2020RGB-3CJH-TX1812Z5")
      (fields (field (name "Manufacturer") "TCWIN"))
      (libsource (lib "") (part "TC2020RGB-3CJH-TX1812Z5"))
    )
    (comp (ref "LED185")
      (value "TC2020RGB-3CJH-TX1812Z5")
      (fields (field (name "Manufacturer") "TCWIN"))
      (libsource (lib "") (part "TC2020RGB-3CJH-TX1812Z5"))
    )
    (comp (ref "LED186")
      (value "TC2020RGB-3CJH-TX1812Z5")
      (fields (field (name "Manufacturer") "TCWIN"))
      (libsource (lib "") (part "TC2020RGB-3CJH-TX1812Z5"))
    )
    (comp (ref "LED187")
      (value "TC2020RGB-3CJH-TX1812Z5")
      (fields (field (name "Manufacturer") "TCWIN"))
      (libsource (lib "") (part "TC2020RGB-3CJH-TX1812Z5"))
    )
    (comp (ref "LED188")
      (value "TC2020RGB-3CJH-TX1812Z5")
      (fields (field (name "Manufacturer") "TCWIN"))
      (libsource (lib "") (part "TC2020RGB-3CJH-TX1812Z5"))
    )
    (comp (ref "LED189")
      (value "TC2020RGB-3CJH-TX1812Z5")
      (fields (field (name "Manufacturer") "TCWIN"))
      (libsource (lib "") (part "TC2020RGB-3CJH-TX1812Z5"))
    )
    (comp (ref "LED190")
      (value "TC2020RGB-3CJH-TX1812Z5")
      (fields (field (name "Manufacturer") "TCWIN"))
      (libsource (lib "") (part "TC2020RGB-3CJH-TX1812Z5"))
    )
    (comp (ref "LED191")
      (value "TC2020RGB-3CJH-TX1812Z5")
      (fields (field (name "Manufacturer") "TCWIN"))
      (libsource (lib "") (part "TC2020RGB-3CJH-TX1812Z5"))
    )
    (comp (ref "LED192")
      (value "TC2020RGB-3CJH-TX1812Z5")
      (fields (field (name "Manufacturer") "TCWIN"))
      (libsource (lib "") (part "TC2020RGB-3CJH-TX1812Z5"))
    )
    (comp (ref "LED193")
      (value "TC2020RGB-3CJH-TX1812Z5")
      (fields (field (name "Manufacturer") "TCWIN"))
      (libsource (lib "") (part "TC2020RGB-3CJH-TX1812Z5"))
    )
    (comp (ref "LED194")
      (value "TC2020RGB-3CJH-TX1812Z5")
      (fields (field (name "Manufacturer") "TCWIN"))
      (libsource (lib "") (part "TC2020RGB-3CJH-TX1812Z5"))
    )
    (comp (ref "LED195")
      (value "TC2020RGB-3CJH-TX1812Z5")
      (fields (field (name "Manufacturer") "TCWIN"))
      (libsource (lib "") (part "TC2020RGB-3CJH-TX1812Z5"))
    )
    (comp (ref "LED196")
      (value "TC2020RGB-3CJH-TX1812Z5")
      (fields (field (name "Manufacturer") "TCWIN"))
      (libsource (lib "") (part "TC2020RGB-3CJH-TX1812Z5"))
    )
    (comp (ref "LED197")
      (value "TC2020RGB-3CJH-TX1812Z5")
      (fields (field (name "Manufacturer") "TCWIN"))
      (libsource (lib "") (part "TC2020RGB-3CJH-TX1812Z5"))
    )
    (comp (ref "LED198")
      (value "TC2020RGB-3CJH-TX1812Z5")
      (fields (field (name "Manufacturer") "TCWIN"))
      (libsource (lib "") (part "TC2020RGB-3CJH-TX1812Z5"))
    )
    (comp (ref "LED199")
      (value "TC2020RGB-3CJH-TX1812Z5")
      (fields (field (name "Manufacturer") "TCWIN"))
      (libsource (lib "") (part "TC2020RGB-3CJH-TX1812Z5"))
    )
    (comp (ref "LED200")
      (value "TC2020RGB-3CJH-TX1812Z5")
      (fields (field (name "Manufacturer") "TCWIN"))
      (libsource (lib "") (part "TC2020RGB-3CJH-TX1812Z5"))
    )
    (comp (ref "LED201")
      (value "TC2020RGB-3CJH-TX1812Z5")
      (fields (field (name "Manufacturer") "TCWIN"))
      (libsource (lib "") (part "TC2020RGB-3CJH-TX1812Z5"))
    )
    (comp (ref "LED202")
      (value "TC2020RGB-3CJH-TX1812Z5")
      (fields (field (name "Manufacturer") "TCWIN"))
      (libsource (lib "") (part "TC2020RGB-3CJH-TX1812Z5"))
    )
    (comp (ref "LED203")
      (value "TC2020RGB-3CJH-TX1812Z5")
      (fields (field (name "Manufacturer") "TCWIN"))
      (libsource (lib "") (part "TC2020RGB-3CJH-TX1812Z5"))
    )
    (comp (ref "LED204")
      (value "TC2020RGB-3CJH-TX1812Z5")
      (fields (field (name "Manufacturer") "TCWIN"))
      (libsource (lib "") (part "TC2020RGB-3CJH-TX1812Z5"))
    )
    (comp (ref "LED205")
      (value "TC2020RGB-3CJH-TX1812Z5")
      (fields (field (name "Manufacturer") "TCWIN"))
      (libsource (lib "") (part "TC2020RGB-3CJH-TX1812Z5"))
    )
    (comp (ref "LED206")
      (value "TC2020RGB-3CJH-TX1812Z5")
      (fields (field (name "Manufacturer") "TCWIN"))
      (libsource (lib "") (part "TC2020RGB-3CJH-TX1812Z5"))
    )
    (comp (ref "LED207")
      (value "TC2020RGB-3CJH-TX1812Z5")
      (fields (field (name "Manufacturer") "TCWIN"))
      (libsource (lib "") (part "TC2020RGB-3CJH-TX1812Z5"))
    )
    (comp (ref "LED208")
      (value "TC2020RGB-3CJH-TX1812Z5")
      (fields (field (name "Manufacturer") "TCWIN"))
      (libsource (lib "") (part "TC2020RGB-3CJH-TX1812Z5"))
    )
    (comp (ref "LED209")
      (value "TC2020RGB-3CJH-TX1812Z5")
      (fields (field (name "Manufacturer") "TCWIN"))
      (libsource (lib "") (part "TC2020RGB-3CJH-TX1812Z5"))
    )
    (comp (ref "LED210")
      (value "TC2020RGB-3CJH-TX1812Z5")
      (fields (field (name "Manufacturer") "TCWIN"))
      (libsource (lib "") (part "TC2020RGB-3CJH-TX1812Z5"))
    )
    (comp (ref "LED211")
      (value "TC2020RGB-3CJH-TX1812Z5")
      (fields (field (name "Manufacturer") "TCWIN"))
      (libsource (lib "") (part "TC2020RGB-3CJH-TX1812Z5"))
    )
    (comp (ref "LED212")
      (value "TC2020RGB-3CJH-TX1812Z5")
      (fields (field (name "Manufacturer") "TCWIN"))
      (libsource (lib "") (part "TC2020RGB-3CJH-TX1812Z5"))
    )
    (comp (ref "LED213")
      (value "TC2020RGB-3CJH-TX1812Z5")
      (fields (field (name "Manufacturer") "TCWIN"))
      (libsource (lib "") (part "TC2020RGB-3CJH-TX1812Z5"))
    )
    (comp (ref "LED214")
      (value "TC2020RGB-3CJH-TX1812Z5")
      (fields (field (name "Manufacturer") "TCWIN"))
      (libsource (lib "") (part "TC2020RGB-3CJH-TX1812Z5"))
    )
    (comp (ref "LED215")
      (value "TC2020RGB-3CJH-TX1812Z5")
      (fields (field (name "Manufacturer") "TCWIN"))
      (libsource (lib "") (part "TC2020RGB-3CJH-TX1812Z5"))
    )
    (comp (ref "LED216")
      (value "TC2020RGB-3CJH-TX1812Z5")
      (fields (field (name "Manufacturer") "TCWIN"))
      (libsource (lib "") (part "TC2020RGB-3CJH-TX1812Z5"))
    )
    (comp (ref "LED217")
      (value "TC2020RGB-3CJH-TX1812Z5")
      (fields (field (name "Manufacturer") "TCWIN"))
      (libsource (lib "") (part "TC2020RGB-3CJH-TX1812Z5"))
    )
    (comp (ref "LED218")
      (value "TC2020RGB-3CJH-TX1812Z5")
      (fields (field (name "Manufacturer") "TCWIN"))
      (libsource (lib "") (part "TC2020RGB-3CJH-TX1812Z5"))
    )
    (comp (ref "LED219")
      (value "TC2020RGB-3CJH-TX1812Z5")
      (fields (field (name "Manufacturer") "TCWIN"))
      (libsource (lib "") (part "TC2020RGB-3CJH-TX1812Z5"))
    )
    (comp (ref "LED220")
      (value "TC2020RGB-3CJH-TX1812Z5")
      (fields (field (name "Manufacturer") "TCWIN"))
      (libsource (lib "") (part "TC2020RGB-3CJH-TX1812Z5"))
    )
    (comp (ref "LED221")
      (value "TC2020RGB-3CJH-TX1812Z5")
      (fields (field (name "Manufacturer") "TCWIN"))
      (libsource (lib "") (part "TC2020RGB-3CJH-TX1812Z5"))
    )
    (comp (ref "LED222")
      (value "TC2020RGB-3CJH-TX1812Z5")
      (fields (field (name "Manufacturer") "TCWIN"))
      (libsource (lib "") (part "TC2020RGB-3CJH-TX1812Z5"))
    )
    (comp (ref "LED223")
      (value "TC2020RGB-3CJH-TX1812Z5")
      (fields (field (name "Manufacturer") "TCWIN"))
      (libsource (lib "") (part "TC2020RGB-3CJH-TX1812Z5"))
    )
    (comp (ref "Q1")
      (value "ALS-PT19-315C/L177/TR8")
      (fields (field (name "Manufacturer") "EVERLIGHT"))
      (libsource (lib "") (part "ALS-PT19-315C/L177/TR8"))
    )
    (comp (ref "R1")
      (value "1K")
      (fields (field (name "Manufacturer Part") "0402WGF1001TCE") (field (name "Manufacturer") "UniOhm"))
      (libsource (lib "") (part "0402WGF1001TCE"))
    )
    (comp (ref "R2")
      (value "1K")
      (fields (field (name "Manufacturer Part") "0402WGF1001TCE") (field (name "Manufacturer") "UniOhm"))
      (libsource (lib "") (part "0402WGF1001TCE"))
    )
    (comp (ref "R3")
      (value "1K")
      (fields (field (name "Manufacturer Part") "0402WGF1001TCE") (field (name "Manufacturer") "UniOhm"))
      (libsource (lib "") (part "0402WGF1001TCE_1"))
    )
    (comp (ref "R4")
      (value "470")
      (fields (field (name "Manufacturer Part") "0402WGF4700TCE") (field (name "Manufacturer") "UniOhm"))
      (libsource (lib "") (part "0402WGF4700TCE"))
    )
    (comp (ref "R5")
      (value "20k")
      (fields (field (name "Manufacturer Part") "0402WGF2002TCE") (field (name "Manufacturer") "UniOhm"))
      (libsource (lib "") (part "0402WGF2002TCE"))
    )
    (comp (ref "R6")
      (value "10K")
      (fields (field (name "Manufacturer Part") "0402WGF1002TCE") (field (name "Manufacturer") "UniOhm"))
      (libsource (lib "") (part "0402WGF1002TCE_1"))
    )
    (comp (ref "R7")
      (value "10K")
      (fields (field (name "Manufacturer Part") "0402WGF1002TCE") (field (name "Manufacturer") "UniOhm"))
      (libsource (lib "") (part "0402WGF1002TCE"))
    )
    (comp (ref "R8")
      (value "10K")
      (fields (field (name "Manufacturer Part") "0402WGF1002TCE") (field (name "Manufacturer") "UniOhm"))
      (libsource (lib "") (part "0402WGF1002TCE"))
    )
    (comp (ref "R9")
      (value "5.1K")
      (fields (field (name "Manufacturer Part") "0402WGF5101TCE") (field (name "Manufacturer") "UniOhm"))
      (libsource (lib "") (part "0402WGF5101TCE"))
    )
    (comp (ref "R10")
      (value "5.1K")
      (fields (field (name "Manufacturer Part") "0402WGF5101TCE") (field (name "Manufacturer") "UniOhm"))
      (libsource (lib "") (part "0402WGF5101TCE"))
    )
    (comp (ref "SC1")
      (value "70mF")
      (fields (field (name "Manufacturer Part") "SM3R3703T01U") (field (name "Manufacturer") "KORCHIP(高奇普)"))
      (libsource (lib "") (part "SM3R3703T01U"))
    )
    (comp (ref "SW1")
      (value "TS-1088-AR02016")
      (fields (field (name "Manufacturer") "XUNPU"))
      (libsource (lib "") (part "TS-1088-AR02016"))
    )
    (comp (ref "U1")
      (value "SN74LV1T34DBVR")
      (fields (field (name "Manufacturer") "TI"))
      (libsource (lib "") (part "SN74LV1T34DBVR"))
    )
    (comp (ref "U2")
      (value "PCF8563T")
      (fields (field (name "Manufacturer Part") "PCF8563T/5,518") (field (name "Manufacturer") "NXP"))
      (libsource (lib "") (part "PCF8563T/5,518"))
    )
    (comp (ref "U3")
      (value "AMS1117-3.3")
      (fields (field (name "Manufacturer") "AMS"))
      (libsource (lib "") (part "AMS1117-3.3"))
    )
    (comp (ref "U4")
      (value "ESP32-C3-MINI-1")
      (fields
        (field (name "Manufacturer Part") "ESP32-C3-MINI-1-N4")
        (field (name "Manufacturer") "ESPRESSIF 乐鑫")
      )
      (libsource (lib "") (part "ESP32-C3-MINI-1-N4"))
    )
    (comp (ref "USBC1")
      (value "USB3.1C16PFSMT")
      (fields (field (name "Manufacturer") "LCSC"))
      (libsource (lib "") (part "USB3.1C16PFSMT"))
    )
    (comp (ref "X1")
      (value "32.768KHz")
      (fields (field (name "Manufacturer Part") "Q13FC1350000400") (field (name "Manufacturer") "EPSON"))
      (libsource (lib "") (part "Q13FC1350000400"))
    )
  )
  (nets
    (net (code "1") (name "+3.3V") (class "Default")
      (node (ref "C10") (pin "2") (pinfunction "2_2") (pintype "input"))
      (node (ref "C12") (pin "1") (pinfunction "1_1") (pintype "unspecified"))
      (node (ref "C5") (pin "2") (pinfunction "2_2") (pintype "input"))
      (node (ref "C6") (pin "2") (pinfunction "2_2") (pintype "input"))
      (node (ref "C9") (pin "2") (pinfunction "2_2") (pintype "input"))
      (node (ref "CN1") (pin "2") (pinfunction "2_2") (pintype "unspecified"))
      (node (ref "D5") (pin "2") (pinfunction "+_2") (pintype "unspecified"))
      (node (ref "H1") (pin "3") (pinfunction "3_3") (pintype "unspecified"))
      (node (ref "Q1") (pin "1") (pinfunction "C1_1") (pintype "unspecified"))
      (node (ref "R1") (pin "1") (pinfunction "1_1") (pintype "input"))
      (node (ref "R2") (pin "1") (pinfunction "1_1") (pintype "input"))
      (node (ref "R6") (pin "2") (pinfunction "2_2") (pintype "input"))
      (node (ref "R7") (pin "1") (pinfunction "1_1") (pintype "input"))
      (node (ref "R8") (pin "1") (pinfunction "1_1") (pintype "input"))
      (node (ref "U3") (pin "2") (pinfunction "Vout_2") (pintype "unspecified"))
      (node (ref "U4") (pin "3") (pinfunction "3V3_3") (pintype "unspecified"))
    )
    (net (code "2") (name "+5V") (class "Default")
      (node (ref "C3") (pin "2") (pinfunction "2_2") (pintype "input"))
      (node (ref "C4") (pin "2") (pinfunction "2_2") (pintype "input"))
      (node (ref "C7") (pin "2") (pinfunction "2_2") (pintype "input"))
      (node (ref "C8") (pin "2") (pinfunction "2_2") (pintype "input"))
      (node (ref "D4") (pin "1") (pinfunction "-_1") (pintype "unspecified"))
      (node (ref "H1") (pin "2") (pinfunction "2_2") (pintype "unspecified"))
      (node (ref "LED1") (pin "2") (pinfunction "VDD_2") (pintype "unspecified"))
      (node (ref "LED10") (pin "2") (pinfunction "VDD_2") (pintype "unspecified"))
      (node (ref "LED100") (pin "2") (pinfunction "VDD_2") (pintype "unspecified"))
      (node (ref "LED101") (pin "2") (pinfunction "VDD_2") (pintype "unspecified"))
      (node (ref "LED102") (pin "2") (pinfunction "VDD_2") (pintype "unspecified"))
      (node (ref "LED103") (pin "2") (pinfunction "VDD_2") (pintype "unspecified"))
      (node (ref "LED104") (pin "2") (pinfunction "VDD_2") (pintype "unspecified"))
      (node (ref "LED105") (pin "2") (pinfunction "VDD_2") (pintype "unspecified"))
      (node (ref "LED106") (pin "2") (pinfunction "VDD_2") (pintype "unspecified"))
      (node (ref "LED107") (pin "2") (pinfunction "VDD_2") (pintype "unspecified"))
      (node (ref "LED108") (pin "2") (pinfunction "VDD_2") (pintype "unspecified"))
      (node (ref "LED109") (pin "2") (pinfunction "VDD_2") (pintype "unspecified"))
      (node (ref "LED11") (pin "2") (pinfunction "VDD_2") (pintype "unspecified"))
      (node (ref "LED110") (pin "2") (pinfunction "VDD_2") (pintype "unspecified"))
      (node (ref "LED111") (pin "2") (pinfunction "VDD_2") (pintype "unspecified"))
      (node (ref "LED112") (pin "2") (pinfunction "VDD_2") (pintype "unspecified"))
      (node (ref "LED113") (pin "2") (pinfunction "VDD_2") (pintype "unspecified"))
      (node (ref "LED114") (pin "2") (pinfunction "VDD_2") (pintype "unspecified"))
      (node (ref "LED115") (pin "2") (pinfunction "VDD_2") (pintype "unspecified"))
      (node (ref "LED116") (pin "2") (pinfunction "VDD_2") (pintype "unspecified"))
      (node (ref "LED117") (pin "2") (pinfunction "VDD_2") (pintype "unspecified"))
      (node (ref "LED118") (pin "2") (pinfunction "VDD_2") (pintype "unspecified"))
      (node (ref "LED119") (pin "2") (pinfunction "VDD_2") (pintype "unspecified"))
      (node (ref "LED12") (pin "2") (pinfunction "VDD_2") (pintype "unspecified"))
      (node (ref "LED120") (pin "2") (pinfunction "VDD_2") (pintype "unspecified"))
      (node (ref "LED121") (pin "2") (pinfunction "VDD_2") (pintype "unspecified"))
      (node (ref "LED122") (pin "2") (pinfunction "VDD_2") (pintype "unspecified"))
      (node (ref "LED123") (pin "2") (pinfunction "VDD_2") (pintype "unspecified"))
      (node (ref "LED124") (pin "2") (pinfunction "VDD_2") (pintype "unspecified"))
      (node (ref "LED125") (pin "2") (pinfunction "VDD_2") (pintype "unspecified"))
      (node (ref "LED126") (pin "2") (pinfunction "VDD_2") (pintype "unspecified"))
      (node (ref "LED127") (pin "2") (pinfunction "VDD_2") (pintype "unspecified"))
      (node (ref "LED128") (pin "2") (pinfunction "VDD_2") (pintype "unspecified"))
      (node (ref "LED129") (pin "2") (pinfunction "VDD_2") (pintype "unspecified"))
      (node (ref "LED13") (pin "2") (pinfunction "VDD_2") (pintype "unspecified"))
      (node (ref "LED130") (pin "2") (pinfunction "VDD_2") (pintype "unspecified"))
      (node (ref "LED131") (pin "2") (pinfunction "VDD_2") (pintype "unspecified"))
      (node (ref "LED132") (pin "2") (pinfunction "VDD_2") (pintype "unspecified"))
      (node (ref "LED133") (pin "2") (pinfunction "VDD_2") (pintype "unspecified"))
      (node (ref "LED134") (pin "2") (pinfunction "VDD_2") (pintype "unspecified"))
      (node (ref "LED135") (pin "2") (pinfunction "VDD_2") (pintype "unspecified"))
      (node (ref "LED136") (pin "2") (pinfunction "VDD_2") (pintype "unspecified"))
      (node (ref "LED137") (pin "2") (pinfunction "VDD_2") (pintype "unspecified"))
      (node (ref "LED138") (pin "2") (pinfunction "VDD_2") (pintype "unspecified"))
      (node (ref "LED139") (pin "2") (pinfunction "VDD_2") (pintype "unspecified"))
      (node (ref "LED14") (pin "2") (pinfunction "VDD_2") (pintype "unspecified"))
      (node (ref "LED140") (pin "2") (pinfunction "VDD_2") (pintype "unspecified"))
      (node (ref "LED141") (pin "2") (pinfunction "VDD_2") (pintype "unspecified"))
      (node (ref "LED142") (pin "2") (pinfunction "VDD_2") (pintype "unspecified"))
      (node (ref "LED143") (pin "2") (pinfunction "VDD_2") (pintype "unspecified"))
      (node (ref "LED144") (pin "2") (pinfunction "VDD_2") (pintype "unspecified"))
      (node (ref "LED145") (pin "2") (pinfunction "VDD_2") (pintype "unspecified"))
      (node (ref "LED146") (pin "2") (pinfunction "VDD_2") (pintype "unspecified"))
      (node (ref "LED147") (pin "2") (pinfunction "VDD_2") (pintype "unspecified"))
      (node (ref "LED148") (pin "2") (pinfunction "VDD_2") (pintype "unspecified"))
      (node (ref "LED149") (pin "2") (pinfunction "VDD_2") (pintype "unspecified"))
      (node (ref "LED15") (pin "2") (pinfunction "VDD_2") (pintype "unspecified"))
      (node (ref "LED150") (pin "2") (pinfunction "VDD_2") (pintype "unspecified"))
      (node (ref "LED151") (pin "2") (pinfunction "VDD_2") (pintype "unspecified"))
      (node (ref "LED152") (pin "2") (pinfunction "VDD_2") (pintype "unspecified"))
      (node (ref "LED153") (pin "2") (pinfunction "VDD_2") (pintype "unspecified"))
      (node (ref "LED154") (pin "2") (pinfunction "VDD_2") (pintype "unspecified"))
      (node (ref "LED155") (pin "2") (pinfunction "VDD_2") (pintype "unspecified"))
      (node (ref "LED156") (pin "2") (pinfunction "VDD_2") (pintype "unspecified"))
      (node (ref "LED157") (pin "2") (pinfunction "VDD_2") (pintype "unspecified"))
      (node (ref "LED158") (pin "2") (pinfunction "VDD_2") (pintype "unspecified"))
      (node (ref "LED159") (pin "2") (pinfunction "VDD_2") (pintype "unspecified"))
      (node (ref "LED16") (pin "2") (pinfunction "VDD_2") (pintype "unspecified"))
      (node (ref "LED160") (pin "2") (pinfunction "VDD_2") (pintype "unspecified"))
      (node (ref "LED161") (pin "2") (pinfunction "VDD_2") (pintype "unspecified"))
      (node (ref "LED162") (pin "2") (pinfunction "VDD_2") (pintype "unspecified"))
      (node (ref "LED163") (pin "2") (pinfunction "VDD_2") (pintype "unspecified"))
      (node (ref "LED164") (pin "2") (pinfunction "VDD_2") (pintype "unspecified"))
      (node (ref "LED165") (pin "2") (pinfunction "VDD_2") (pintype "unspecified"))
      (node (ref "LED166") (pin "2") (pinfunction "VDD_2") (pintype "unspecified"))
      (node (ref "LED167") (pin "2") (pinfunction "VDD_2") (pintype "unspecified"))
      (node (ref "LED168") (pin "2") (pinfunction "VDD_2") (pintype "unspecified"))
      (node (ref "LED169") (pin "2") (pinfunction "VDD_2") (pintype "unspecified"))
      (node (ref "LED17") (pin "2") (pinfunction "VDD_2") (pintype "unspecified"))
      (node (ref "LED170") (pin "2") (pinfunction "VDD_2") (pintype "unspecified"))
      (node (ref "LED171") (pin "2") (pinfunction "VDD_2") (pintype "unspecified"))
      (node (ref "LED172") (pin "2") (pinfunction "VDD_2") (pintype "unspecified"))
      (node (ref "LED173") (pin "2") (pinfunction "VDD_2") (pintype "unspecified"))
      (node (ref "LED174") (pin "2") (pinfunction "VDD_2") (pintype "unspecified"))
      (node (ref "LED175") (pin "2") (pinfunction "VDD_2") (pintype "unspecified"))
      (node (ref "LED176") (pin "2") (pinfunction "VDD_2") (pintype "unspecified"))
      (node (ref "LED177") (pin "2") (pinfunction "VDD_2") (pintype "unspecified"))
      (node (ref "LED178") (pin "2") (pinfunction "VDD_2") (pintype "unspecified"))
      (node (ref "LED179") (pin "2") (pinfunction "VDD_2") (pintype "unspecified"))
      (node (ref "LED18") (pin "2") (pinfunction "VDD_2") (pintype "unspecified"))
      (node (ref "LED180") (pin "2") (pinfunction "VDD_2") (pintype "unspecified"))
      (node (ref "LED181") (pin "2") (pinfunction "VDD_2") (pintype "unspecified"))
      (node (ref "LED182") (pin "2") (pinfunction "VDD_2") (pintype "unspecified"))
      (node (ref "LED183") (pin "2") (pinfunction "VDD_2") (pintype "unspecified"))
      (node (ref "LED184") (pin "2") (pinfunction "VDD_2") (pintype "unspecified"))
      (node (ref "LED185") (pin "2") (pinfunction "VDD_2") (pintype "unspecified"))
      (node (ref "LED186") (pin "2") (pinfunction "VDD_2") (pintype "unspecified"))
      (node (ref "LED187") (pin "2") (pinfunction "VDD_2") (pintype "unspecified"))
      (node (ref "LED188") (pin "2") (pinfunction "VDD_2") (pintype "unspecified"))
      (node (ref "LED189") (pin "2") (pinfunction "VDD_2") (pintype "unspecified"))
      (node (ref "LED19") (pin "2") (pinfunction "VDD_2") (pintype "unspecified"))
      (node (ref "LED190") (pin "2") (pinfunction "VDD_2") (pintype "unspecified"))
      (node (ref "LED191") (pin "2") (pinfunction "VDD_2") (pintype "unspecified"))
      (node (ref "LED192") (pin "2") (pinfunction "VDD_2") (pintype "unspecified"))
      (node (ref "LED193") (pin "2") (pinfunction "VDD_2") (pintype "unspecified"))
      (node (ref "LED194") (pin "2") (pinfunction "VDD_2") (pintype "unspecified"))
      (node (ref "LED195") (pin "2") (pinfunction "VDD_2") (pintype "unspecified"))
      (node (ref "LED196") (pin "2") (pinfunction "VDD_2") (pintype "unspecified"))
      (node (ref "LED197") (pin "2") (pinfunction "VDD_2") (pintype "unspecified"))
      (node (ref "LED198") (pin "2") (pinfunction "VDD_2") (pintype "unspecified"))
      (node (ref "LED199") (pin "2") (pinfunction "VDD_2") (pintype "unspecified"))
      (node (ref "LED2") (pin "2") (pinfunction "VDD_2") (pintype "unspecified"))
      (node (ref "LED20") (pin "2") (pinfunction "VDD_2") (pintype "unspecified"))
      (node (ref "LED200") (pin "2") (pinfunction "VDD_2") (pintype "unspecified"))
      (node (ref "LED201") (pin "2") (pinfunction "VDD_2") (pintype "unspecified"))
      (node (ref "LED202") (pin "2") (pinfunction "VDD_2") (pintype "unspecified"))
      (node (ref "LED203") (pin "2") (pinfunction "VDD_2") (pintype "unspecified"))
      (node (ref "LED204") (pin "2") (pinfunction "VDD_2") (pintype "unspecified"))
      (node (ref "LED205") (pin "2") (pinfunction "VDD_2") (pintype "unspecified"))
      (node (ref "LED206") (pin "2") (pinfunction "VDD_2") (pintype "unspecified"))
      (node (ref "LED207") (pin "2") (pinfunction "VDD_2") (pintype "unspecified"))
      (node (ref "LED208") (pin "2") (pinfunction "VDD_2") (pintype "unspecified"))
      (node (ref "LED209") (pin "2") (pinfunction "VDD_2") (pintype "unspecified"))
      (node (ref "LED21") (pin "2") (pinfunction "VDD_2") (pintype "unspecified"))
      (node (ref "LED210") (pin "2") (pinfunction "VDD_2") (pintype "unspecified"))
      (node (ref "LED211") (pin "2") (pinfunction "VDD_2") (pintype "unspecified"))
      (node (ref "LED212") (pin "2") (pinfunction "VDD_2") (pintype "unspecified"))
      (node (ref "LED213") (pin "2") (pinfunction "VDD_2") (pintype "unspecified"))
      (node (ref "LED214") (pin "2") (pinfunction "VDD_2") (pintype "unspecified"))
      (node (ref "LED215") (pin "2") (pinfunction "VDD_2") (pintype "unspecified"))
      (node (ref "LED216") (pin "2") (pinfunction "VDD_2") (pintype "unspecified"))
      (node (ref "LED217") (pin "2") (pinfunction "VDD_2") (pintype "unspecified"))
      (node (ref "LED218") (pin "2") (pinfunction "VDD_2") (pintype "unspecified"))
      (node (ref "LED219") (pin "2") (pinfunction "VDD_2") (pintype "unspecified"))
      (node (ref "LED22") (pin "2") (pinfunction "VDD_2") (pintype "unspecified"))
      (node (ref "LED220") (pin "2") (pinfunction "VDD_2") (pintype "unspecified"))
      (node (ref "LED221") (pin "2") (pinfunction "VDD_2") (pintype "unspecified"))
      (node (ref "LED222") (pin "2") (pinfunction "VDD_2") (pintype "unspecified"))
      (node (ref "LED223") (pin "2") (pinfunction "VDD_2") (pintype "unspecified"))
      (node (ref "LED23") (pin "2") (pinfunction "VDD_2") (pintype "unspecified"))
      (node (ref "LED24") (pin "2") (pinfunction "VDD_2") (pintype "unspecified"))
      (node (ref "LED25") (pin "2") (pinfunction "VDD_2") (pintype "unspecified"))
      (node (ref "LED26") (pin "2") (pinfunction "VDD_2") (pintype "unspecified"))
      (node (ref "LED27") (pin "2") (pinfunction "VDD_2") (pintype "unspecified"))
      (node (ref "LED28") (pin "2") (pinfunction "VDD_2") (pintype "unspecified"))
      (node (ref "LED29") (pin "2") (pinfunction "VDD_2") (pintype "unspecified"))
      (node (ref "LED3") (pin "2") (pinfunction "VDD_2") (pintype "unspecified"))
      (node (ref "LED30") (pin "2") (pinfunction "VDD_2") (pintype "unspecified"))
      (node (ref "LED31") (pin "2") (pinfunction "VDD_2") (pintype "unspecified"))
      (node (ref "LED32") (pin "2") (pinfunction "VDD_2") (pintype "unspecified"))
      (node (ref "LED33") (pin "2") (pinfunction "VDD_2") (pintype "unspecified"))
      (node (ref "LED34") (pin "2") (pinfunction "VDD_2") (pintype "unspecified"))
      (node (ref "LED35") (pin "2") (pinfunction "VDD_2") (pintype "unspecified"))
      (node (ref "LED36") (pin "2") (pinfunction "VDD_2") (pintype "unspecified"))
      (node (ref "LED37") (pin "2") (pinfunction "VDD_2") (pintype "unspecified"))
      (node (ref "LED38") (pin "2") (pinfunction "VDD_2") (pintype "unspecified"))
      (node (ref "LED39") (pin "2") (pinfunction "VDD_2") (pintype "unspecified"))
      (node (ref "LED4") (pin "2") (pinfunction "VDD_2") (pintype "unspecified"))
      (node (ref "LED40") (pin "2") (pinfunction "VDD_2") (pintype "unspecified"))
      (node (ref "LED41") (pin "2") (pinfunction "VDD_2") (pintype "unspecified"))
      (node (ref "LED42") (pin "2") (pinfunction "VDD_2") (pintype "unspecified"))
      (node (ref "LED43") (pin "2") (pinfunction "VDD_2") (pintype "unspecified"))
      (node (ref "LED44") (pin "2") (pinfunction "VDD_2") (pintype "unspecified"))
      (node (ref "LED45") (pin "2") (pinfunction "VDD_2") (pintype "unspecified"))
      (node (ref "LED46") (pin "2") (pinfunction "VDD_2") (pintype "unspecified"))
      (node (ref "LED47") (pin "2") (pinfunction "VDD_2") (pintype "unspecified"))
      (node (ref "LED48") (pin "2") (pinfunction "VDD_2") (pintype "unspecified"))
      (node (ref "LED49") (pin "2") (pinfunction "VDD_2") (pintype "unspecified"))
      (node (ref "LED5") (pin "2") (pinfunction "VDD_2") (pintype "unspecified"))
      (node (ref "LED50") (pin "2") (pinfunction "VDD_2") (pintype "unspecified"))
      (node (ref "LED51") (pin "2") (pinfunction "VDD_2") (pintype "unspecified"))
      (node (ref "LED52") (pin "2") (pinfunction "VDD_2") (pintype "unspecified"))
      (node (ref "LED53") (pin "2") (pinfunction "VDD_2") (pintype "unspecified"))
      (node (ref "LED54") (pin "2") (pinfunction "VDD_2") (pintype "unspecified"))
      (node (ref "LED55") (pin "2") (pinfunction "VDD_2") (pintype "unspecified"))
      (node (ref "LED56") (pin "2") (pinfunction "VDD_2") (pintype "unspecified"))
      (node (ref "LED57") (pin "2") (pinfunction "VDD_2") (pintype "unspecified"))
      (node (ref "LED58") (pin "2") (pinfunction "VDD_2") (pintype "unspecified"))
      (node (ref "LED59") (pin "2") (pinfunction "VDD_2") (pintype "unspecified"))
      (node (ref "LED6") (pin "2") (pinfunction "VDD_2") (pintype "unspecified"))
      (node (ref "LED60") (pin "2") (pinfunction "VDD_2") (pintype "unspecified"))
      (node (ref "LED61") (pin "2") (pinfunction "VDD_2") (pintype "unspecified"))
      (node (ref "LED62") (pin "2") (pinfunction "VDD_2") (pintype "unspecified"))
      (node (ref "LED63") (pin "2") (pinfunction "VDD_2") (pintype "unspecified"))
      (node (ref "LED64") (pin "2") (pinfunction "VDD_2") (pintype "unspecified"))
      (node (ref "LED65") (pin "2") (pinfunction "VDD_2") (pintype "unspecified"))
      (node (ref "LED66") (pin "2") (pinfunction "VDD_2") (pintype "unspecified"))
      (node (ref "LED67") (pin "2") (pinfunction "VDD_2") (pintype "unspecified"))
      (node (ref "LED68") (pin "2") (pinfunction "VDD_2") (pintype "unspecified"))
      (node (ref "LED69") (pin "2") (pinfunction "VDD_2") (pintype "unspecified"))
      (node (ref "LED7") (pin "2") (pinfunction "VDD_2") (pintype "unspecified"))
      (node (ref "LED70") (pin "2") (pinfunction "VDD_2") (pintype "unspecified"))
      (node (ref "LED71") (pin "2") (pinfunction "VDD_2") (pintype "unspecified"))
      (node (ref "LED72") (pin "2") (pinfunction "VDD_2") (pintype "unspecified"))
      (node (ref "LED73") (pin "2") (pinfunction "VDD_2") (pintype "unspecified"))
      (node (ref "LED74") (pin "2") (pinfunction "VDD_2") (pintype "unspecified"))
      (node (ref "LED75") (pin "2") (pinfunction "VDD_2") (pintype "unspecified"))
      (node (ref "LED76") (pin "2") (pinfunction "VDD_2") (pintype "unspecified"))
      (node (ref "LED77") (pin "2") (pinfunction "VDD_2") (pintype "unspecified"))
      (node (ref "LED78") (pin "2") (pinfunction "VDD_2") (pintype "unspecified"))
      (node (ref "LED79") (pin "2") (pinfunction "VDD_2") (pintype "unspecified"))
      (node (ref "LED8") (pin "2") (pinfunction "VDD_2") (pintype "unspecified"))
      (node (ref "LED80") (pin "2") (pinfunction "VDD_2") (pintype "unspecified"))
      (node (ref "LED81") (pin "2") (pinfunction "VDD_2") (pintype "unspecified"))
      (node (ref "LED82") (pin "2") (pinfunction "VDD_2") (pintype "unspecified"))
      (node (ref "LED83") (pin "2") (pinfunction "VDD_2") (pintype "unspecified"))
      (node (ref "LED84") (pin "2") (pinfunction "VDD_2") (pintype "unspecified"))
      (node (ref "LED85") (pin "2") (pinfunction "VDD_2") (pintype "unspecified"))
      (node (ref "LED86") (pin "2") (pinfunction "VDD_2") (pintype "unspecified"))
      (node (ref "LED87") (pin "2") (pinfunction "VDD_2") (pintype "unspecified"))
      (node (ref "LED88") (pin "2") (pinfunction "VDD_2") (pintype "unspecified"))
      (node (ref "LED89") (pin "2") (pinfunction "VDD_2") (pintype "unspecified"))
      (node (ref "LED9") (pin "2") (pinfunction "VDD_2") (pintype "unspecified"))
      (node (ref "LED90") (pin "2") (pinfunction "VDD_2") (pintype "unspecified"))
      (node (ref "LED91") (pin "2") (pinfunction "VDD_2") (pintype "unspecified"))
      (node (ref "LED92") (pin "2") (pinfunction "VDD_2") (pintype "unspecified"))
      (node (ref "LED93") (pin "2") (pinfunction "VDD_2") (pintype "unspecified"))
      (node (ref "LED94") (pin "2") (pinfunction "VDD_2") (pintype "unspecified"))
      (node (ref "LED95") (pin "2") (pinfunction "VDD_2") (pintype "unspecified"))
      (node (ref "LED96") (pin "2") (pinfunction "VDD_2") (pintype "unspecified"))
      (node (ref "LED97") (pin "2") (pinfunction "VDD_2") (pintype "unspecified"))
      (node (ref "LED98") (pin "2") (pinfunction "VDD_2") (pintype "unspecified"))
      (node (ref "LED99") (pin "2") (pinfunction "VDD_2") (pintype "unspecified"))
      (node (ref "U1") (pin "5") (pinfunction "VCC_5") (pintype "unspecified"))
      (node (ref "U3") (pin "3") (pinfunction "Vin_3") (pintype "unspecified"))
    )
    (net (code "3") (name "ANA_CLK_LEDS_DIN_5V") (class "Default")
      (node (ref "LED187") (pin "3") (pinfunction "DO_3") (pintype "unspecified"))
      (node (ref "LED188") (pin "1") (pinfunction "DIN_1") (pintype "unspecified"))
    )
    (net (code "4") (name "D+") (class "Default")
      (node (ref "D1") (pin "1") (pinfunction "1_1") (pintype "unspecified"))
      (node (ref "U4") (pin "27") (pinfunction "IO19_27") (pintype "unspecified"))
      (node (ref "USBC1") (pin "A6") (pinfunction "DP1_A6") (pintype "unspecified"))
      (node (ref "USBC1") (pin "B6") (pinfunction "DP2_B6") (pintype "unspecified"))
    )
    (net (code "5") (name "D-") (class "Default")
      (node (ref "D2") (pin "1") (pinfunction "1_1") (pintype "unspecified"))
      (node (ref "U4") (pin "26") (pinfunction "IO18_26") (pintype "unspecified"))
      (node (ref "USBC1") (pin "A7") (pinfunction "DN1_A7") (pintype "unspecified"))
      (node (ref "USBC1") (pin "B7") (pinfunction "DN2_B7") (pintype "unspecified"))
    )
    (net (code "6") (name "EN_RESET") (class "Default")
      (node (ref "C1") (pin "1") (pinfunction "1_1") (pintype "unspecified"))
      (node (ref "R6") (pin "1") (pinfunction "1_1") (pintype "input"))
      (node (ref "SW1") (pin "2") (pinfunction "2_2") (pintype "unspecified"))
      (node (ref "U4") (pin "8") (pinfunction "EN_8") (pintype "unspecified"))
    )
    (net (code "7") (name "GND") (class "Default")
      (node (ref "C1") (pin "2") (pinfunction "2_2") (pintype "unspecified"))
      (node (ref "C10") (pin "1") (pinfunction "1_1") (pintype "input"))
      (node (ref "C11") (pin "2") (pinfunction "2_2") (pintype "input"))
      (node (ref "C12") (pin "2") (pinfunction "2_2") (pintype "unspecified"))
      (node (ref "C2") (pin "1") (pinfunction "1_1") (pintype "unspecified"))
      (node (ref "C3") (pin "1") (pinfunction "1_1") (pintype "input"))
      (node (ref "C4") (pin "1") (pinfunction "1_1") (pintype "input"))
      (node (ref "C5") (pin "1") (pinfunction "1_1") (pintype "input"))
      (node (ref "C6") (pin "1") (pinfunction "1_1") (pintype "input"))
      (node (ref "C7") (pin "1") (pinfunction "1_1") (pintype "input"))
      (node (ref "C8") (pin "1") (pinfunction "1_1") (pintype "input"))
      (node (ref "C9") (pin "1") (pinfunction "1_1") (pintype "input"))
      (node (ref "CN1") (pin "1") (pinfunction "1_1") (pintype "unspecified"))
      (node (ref "D1") (pin "2") (pinfunction "2_2") (pintype "unspecified"))
      (node (ref "D2") (pin "2") (pinfunction "2_2") (pintype "unspecified"))
      (node (ref "D3") (pin "2") (pinfunction "2_2") (pintype "unspecified"))
      (node (ref "H1") (pin "1") (pinfunction "1_1") (pintype "unspecified"))
      (node (ref "JOY1") (pin "5") (pinfunction "5_5") (pintype "unspecified"))
      (node (ref "LED1") (pin "4") (pinfunction "GND_4") (pintype "unspecified"))
      (node (ref "LED10") (pin "4") (pinfunction "GND_4") (pintype "unspecified"))
      (node (ref "LED100") (pin "4") (pinfunction "GND_4") (pintype "unspecified"))
      (node (ref "LED101") (pin "4") (pinfunction "GND_4") (pintype "unspecified"))
      (node (ref "LED102") (pin "4") (pinfunction "GND_4") (pintype "unspecified"))
      (node (ref "LED103") (pin "4") (pinfunction "GND_4") (pintype "unspecified"))
      (node (ref "LED104") (pin "4") (pinfunction "GND_4") (pintype "unspecified"))
      (node (ref "LED105") (pin "4") (pinfunction "GND_4") (pintype "unspecified"))
      (node (ref "LED106") (pin "4") (pinfunction "GND_4") (pintype "unspecified"))
      (node (ref "LED107") (pin "4") (pinfunction "GND_4") (pintype "unspecified"))
      (node (ref "LED108") (pin "4") (pinfunction "GND_4") (pintype "unspecified"))
      (node (ref "LED109") (pin "4") (pinfunction "GND_4") (pintype "unspecified"))
      (node (ref "LED11") (pin "4") (pinfunction "GND_4") (pintype "unspecified"))
      (node (ref "LED110") (pin "4") (pinfunction "GND_4") (pintype "unspecified"))
      (node (ref "LED111") (pin "4") (pinfunction "GND_4") (pintype "unspecified"))
      (node (ref "LED112") (pin "4") (pinfunction "GND_4") (pintype "unspecified"))
      (node (ref "LED113") (pin "4") (pinfunction "GND_4") (pintype "unspecified"))
      (node (ref "LED114") (pin "4") (pinfunction "GND_4") (pintype "unspecified"))
      (node (ref "LED115") (pin "4") (pinfunction "GND_4") (pintype "unspecified"))
      (node (ref "LED116") (pin "4") (pinfunction "GND_4") (pintype "unspecified"))
      (node (ref "LED117") (pin "4") (pinfunction "GND_4") (pintype "unspecified"))
      (node (ref "LED118") (pin "4") (pinfunction "GND_4") (pintype "unspecified"))
      (node (ref "LED119") (pin "4") (pinfunction "GND_4") (pintype "unspecified"))
      (node (ref "LED12") (pin "4") (pinfunction "GND_4") (pintype "unspecified"))
      (node (ref "LED120") (pin "4") (pinfunction "GND_4") (pintype "unspecified"))
      (node (ref "LED121") (pin "4") (pinfunction "GND_4") (pintype "unspecified"))
      (node (ref "LED122") (pin "4") (pinfunction "GND_4") (pintype "unspecified"))
      (node (ref "LED123") (pin "4") (pinfunction "GND_4") (pintype "unspecified"))
      (node (ref "LED124") (pin "4") (pinfunction "GND_4") (pintype "unspecified"))
      (node (ref "LED125") (pin "4") (pinfunction "GND_4") (pintype "unspecified"))
      (node (ref "LED126") (pin "4") (pinfunction "GND_4") (pintype "unspecified"))
      (node (ref "LED127") (pin "4") (pinfunction "GND_4") (pintype "unspecified"))
      (node (ref "LED128") (pin "4") (pinfunction "GND_4") (pintype "unspecified"))
      (node (ref "LED129") (pin "4") (pinfunction "GND_4") (pintype "unspecified"))
      (node (ref "LED13") (pin "4") (pinfunction "GND_4") (pintype "unspecified"))
      (node (ref "LED130") (pin "4") (pinfunction "GND_4") (pintype "unspecified"))
      (node (ref "LED131") (pin "4") (pinfunction "GND_4") (pintype "unspecified"))
      (node (ref "LED132") (pin "4") (pinfunction "GND_4") (pintype "unspecified"))
      (node (ref "LED133") (pin "4") (pinfunction "GND_4") (pintype "unspecified"))
      (node (ref "LED134") (pin "4") (pinfunction "GND_4") (pintype "unspecified"))
      (node (ref "LED135") (pin "4") (pinfunction "GND_4") (pintype "unspecified"))
      (node (ref "LED136") (pin "4") (pinfunction "GND_4") (pintype "unspecified"))
      (node (ref "LED137") (pin "4") (pinfunction "GND_4") (pintype "unspecified"))
      (node (ref "LED138") (pin "4") (pinfunction "GND_4") (pintype "unspecified"))
      (node (ref "LED139") (pin "4") (pinfunction "GND_4") (pintype "unspecified"))
      (node (ref "LED14") (pin "4") (pinfunction "GND_4") (pintype "unspecified"))
      (node (ref "LED140") (pin "4") (pinfunction "GND_4") (pintype "unspecified"))
      (node (ref "LED141") (pin "4") (pinfunction "GND_4") (pintype "unspecified"))
      (node (ref "LED142") (pin "4") (pinfunction "GND_4") (pintype "unspecified"))
      (node (ref "LED143") (pin "4") (pinfunction "GND_4") (pintype "unspecified"))
      (node (ref "LED144") (pin "4") (pinfunction "GND_4") (pintype "unspecified"))
      (node (ref "LED145") (pin "4") (pinfunction "GND_4") (pintype "unspecified"))
      (node (ref "LED146") (pin "4") (pinfunction "GND_4") (pintype "unspecified"))
      (node (ref "LED147") (pin "4") (pinfunction "GND_4") (pintype "unspecified"))
      (node (ref "LED148") (pin "4") (pinfunction "GND_4") (pintype "unspecified"))
      (node (ref "LED149") (pin "4") (pinfunction "GND_4") (pintype "unspecified"))
      (node (ref "LED15") (pin "4") (pinfunction "GND_4") (pintype "unspecified"))
      (node (ref "LED150") (pin "4") (pinfunction "GND_4") (pintype "unspecified"))
      (node (ref "LED151") (pin "4") (pinfunction "GND_4") (pintype "unspecified"))
      (node (ref "LED152") (pin "4") (pinfunction "GND_4") (pintype "unspecified"))
      (node (ref "LED153") (pin "4") (pinfunction "GND_4") (pintype "unspecified"))
      (node (ref "LED154") (pin "4") (pinfunction "GND_4") (pintype "unspecified"))
      (node (ref "LED155") (pin "4") (pinfunction "GND_4") (pintype "unspecified"))
      (node (ref "LED156") (pin "4") (pinfunction "GND_4") (pintype "unspecified"))
      (node (ref "LED157") (pin "4") (pinfunction "GND_4") (pintype "unspecified"))
      (node (ref "LED158") (pin "4") (pinfunction "GND_4") (pintype "unspecified"))
      (node (ref "LED159") (pin "4") (pinfunction "GND_4") (pintype "unspecified"))
      (node (ref "LED16") (pin "4") (pinfunction "GND_4") (pintype "unspecified"))
      (node (ref "LED160") (pin "4") (pinfunction "GND_4") (pintype "unspecified"))
      (node (ref "LED161") (pin "4") (pinfunction "GND_4") (pintype "unspecified"))
      (node (ref "LED162") (pin "4") (pinfunction "GND_4") (pintype "unspecified"))
      (node (ref "LED163") (pin "4") (pinfunction "GND_4") (pintype "unspecified"))
      (node (ref "LED164") (pin "4") (pinfunction "GND_4") (pintype "unspecified"))
      (node (ref "LED165") (pin "4") (pinfunction "GND_4") (pintype "unspecified"))
      (node (ref "LED166") (pin "4") (pinfunction "GND_4") (pintype "unspecified"))
      (node (ref "LED167") (pin "4") (pinfunction "GND_4") (pintype "unspecified"))
      (node (ref "LED168") (pin "4") (pinfunction "GND_4") (pintype "unspecified"))
      (node (ref "LED169") (pin "4") (pinfunction "GND_4") (pintype "unspecified"))
      (node (ref "LED17") (pin "4") (pinfunction "GND_4") (pintype "unspecified"))
      (node (ref "LED170") (pin "4") (pinfunction "GND_4") (pintype "unspecified"))
      (node (ref "LED171") (pin "4") (pinfunction "GND_4") (pintype "unspecified"))
      (node (ref "LED172") (pin "4") (pinfunction "GND_4") (pintype "unspecified"))
      (node (ref "LED173") (pin "4") (pinfunction "GND_4") (pintype "unspecified"))
      (node (ref "LED174") (pin "4") (pinfunction "GND_4") (pintype "unspecified"))
      (node (ref "LED175") (pin "4") (pinfunction "GND_4") (pintype "unspecified"))
      (node (ref "LED176") (pin "4") (pinfunction "GND_4") (pintype "unspecified"))
      (node (ref "LED177") (pin "4") (pinfunction "GND_4") (pintype "unspecified"))
      (node (ref "LED178") (pin "4") (pinfunction "GND_4") (pintype "unspecified"))
      (node (ref "LED179") (pin "4") (pinfunction "GND_4") (pintype "unspecified"))
      (node (ref "LED18") (pin "4") (pinfunction "GND_4") (pintype "unspecified"))
      (node (ref "LED180") (pin "4") (pinfunction "GND_4") (pintype "unspecified"))
      (node (ref "LED181") (pin "4") (pinfunction "GND_4") (pintype "unspecified"))
      (node (ref "LED182") (pin "4") (pinfunction "GND_4") (pintype "unspecified"))
      (node (ref "LED183") (pin "4") (pinfunction "GND_4") (pintype "unspecified"))
      (node (ref "LED184") (pin "4") (pinfunction "GND_4") (pintype "unspecified"))
      (node (ref "LED185") (pin "4") (pinfunction "GND_4") (pintype "unspecified"))
      (node (ref "LED186") (pin "4") (pinfunction "GND_4") (pintype "unspecified"))
      (node (ref "LED187") (pin "4") (pinfunction "GND_4") (pintype "unspecified"))
      (node (ref "LED188") (pin "4") (pinfunction "GND_4") (pintype "unspecified"))
      (node (ref "LED189") (pin "4") (pinfunction "GND_4") (pintype "unspecified"))
      (node (ref "LED19") (pin "4") (pinfunction "GND_4") (pintype "unspecified"))
      (node (ref "LED190") (pin "4") (pinfunction "GND_4") (pintype "unspecified"))
      (node (ref "LED191") (pin "4") (pinfunction "GND_4") (pintype "unspecified"))
      (node (ref "LED192") (pin "4") (pinfunction "GND_4") (pintype "unspecified"))
      (node (ref "LED193") (pin "4") (pinfunction "GND_4") (pintype "unspecified"))
      (node (ref "LED194") (pin "4") (pinfunction "GND_4") (pintype "unspecified"))
      (node (ref "LED195") (pin "4") (pinfunction "GND_4") (pintype "unspecified"))
      (node (ref "LED196") (pin "4") (pinfunction "GND_4") (pintype "unspecified"))
      (node (ref "LED197") (pin "4") (pinfunction "GND_4") (pintype "unspecified"))
      (node (ref "LED198") (pin "4") (pinfunction "GND_4") (pintype "unspecified"))
      (node (ref "LED199") (pin "4") (pinfunction "GND_4") (pintype "unspecified"))
      (node (ref "LED2") (pin "4") (pinfunction "GND_4") (pintype "unspecified"))
      (node (ref "LED20") (pin "4") (pinfunction "GND_4") (pintype "unspecified"))
      (node (ref "LED200") (pin "4") (pinfunction "GND_4") (pintype "unspecified"))
      (node (ref "LED201") (pin "4") (pinfunction "GND_4") (pintype "unspecified"))
      (node (ref "LED202") (pin "4") (pinfunction "GND_4") (pintype "unspecified"))
      (node (ref "LED203") (pin "4") (pinfunction "GND_4") (pintype "unspecified"))
      (node (ref "LED204") (pin "4") (pinfunction "GND_4") (pintype "unspecified"))
      (node (ref "LED205") (pin "4") (pinfunction "GND_4") (pintype "unspecified"))
      (node (ref "LED206") (pin "4") (pinfunction "GND_4") (pintype "unspecified"))
      (node (ref "LED207") (pin "4") (pinfunction "GND_4") (pintype "unspecified"))
      (node (ref "LED208") (pin "4") (pinfunction "GND_4") (pintype "unspecified"))
      (node (ref "LED209") (pin "4") (pinfunction "GND_4") (pintype "unspecified"))
      (node (ref "LED21") (pin "4") (pinfunction "GND_4") (pintype "unspecified"))
      (node (ref "LED210") (pin "4") (pinfunction "GND_4") (pintype "unspecified"))
      (node (ref "LED211") (pin "4") (pinfunction "GND_4") (pintype "unspecified"))
      (node (ref "LED212") (pin "4") (pinfunction "GND_4") (pintype "unspecified"))
      (node (ref "LED213") (pin "4") (pinfunction "GND_4") (pintype "unspecified"))
      (node (ref "LED214") (pin "4") (pinfunction "GND_4") (pintype "unspecified"))
      (node (ref "LED215") (pin "4") (pinfunction "GND_4") (pintype "unspecified"))
      (node (ref "LED216") (pin "4") (pinfunction "GND_4") (pintype "unspecified"))
      (node (ref "LED217") (pin "4") (pinfunction "GND_4") (pintype "unspecified"))
      (node (ref "LED218") (pin "4") (pinfunction "GND_4") (pintype "unspecified"))
      (node (ref "LED219") (pin "4") (pinfunction "GND_4") (pintype "unspecified"))
      (node (ref "LED22") (pin "4") (pinfunction "GND_4") (pintype "unspecified"))
      (node (ref "LED220") (pin "4") (pinfunction "GND_4") (pintype "unspecified"))
      (node (ref "LED221") (pin "4") (pinfunction "GND_4") (pintype "unspecified"))
      (node (ref "LED222") (pin "4") (pinfunction "GND_4") (pintype "unspecified"))
      (node (ref "LED223") (pin "4") (pinfunction "GND_4") (pintype "unspecified"))
      (node (ref "LED23") (pin "4") (pinfunction "GND_4") (pintype "unspecified"))
      (node (ref "LED24") (pin "4") (pinfunction "GND_4") (pintype "unspecified"))
      (node (ref "LED25") (pin "4") (pinfunction "GND_4") (pintype "unspecified"))
      (node (ref "LED26") (pin "4") (pinfunction "GND_4") (pintype "unspecified"))
      (node (ref "LED27") (pin "4") (pinfunction "GND_4") (pintype "unspecified"))
      (node (ref "LED28") (pin "4") (pinfunction "GND_4") (pintype "unspecified"))
      (node (ref "LED29") (pin "4") (pinfunction "GND_4") (pintype "unspecified"))
      (node (ref "LED3") (pin "4") (pinfunction "GND_4") (pintype "unspecified"))
      (node (ref "LED30") (pin "4") (pinfunction "GND_4") (pintype "unspecified"))
      (node (ref "LED31") (pin "4") (pinfunction "GND_4") (pintype "unspecified"))
      (node (ref "LED32") (pin "4") (pinfunction "GND_4") (pintype "unspecified"))
      (node (ref "LED33") (pin "4") (pinfunction "GND_4") (pintype "unspecified"))
      (node (ref "LED34") (pin "4") (pinfunction "GND_4") (pintype "unspecified"))
      (node (ref "LED35") (pin "4") (pinfunction "GND_4") (pintype "unspecified"))
      (node (ref "LED36") (pin "4") (pinfunction "GND_4") (pintype "unspecified"))
      (node (ref "LED37") (pin "4") (pinfunction "GND_4") (pintype "unspecified"))
      (node (ref "LED38") (pin "4") (pinfunction "GND_4") (pintype "unspecified"))
      (node (ref "LED39") (pin "4") (pinfunction "GND_4") (pintype "unspecified"))
      (node (ref "LED4") (pin "4") (pinfunction "GND_4") (pintype "unspecified"))
      (node (ref "LED40") (pin "4") (pinfunction "GND_4") (pintype "unspecified"))
      (node (ref "LED41") (pin "4") (pinfunction "GND_4") (pintype "unspecified"))
      (node (ref "LED42") (pin "4") (pinfunction "GND_4") (pintype "unspecified"))
      (node (ref "LED43") (pin "4") (pinfunction "GND_4") (pintype "unspecified"))
      (node (ref "LED44") (pin "4") (pinfunction "GND_4") (pintype "unspecified"))
      (node (ref "LED45") (pin "4") (pinfunction "GND_4") (pintype "unspecified"))
      (node (ref "LED46") (pin "4") (pinfunction "GND_4") (pintype "unspecified"))
      (node (ref "LED47") (pin "4") (pinfunction "GND_4") (pintype "unspecified"))
      (node (ref "LED48") (pin "4") (pinfunction "GND_4") (pintype "unspecified"))
      (node (ref "LED49") (pin "4") (pinfunction "GND_4") (pintype "unspecified"))
      (node (ref "LED5") (pin "4") (pinfunction "GND_4") (pintype "unspecified"))
      (node (ref "LED50") (pin "4") (pinfunction "GND_4") (pintype "unspecified"))
      (node (ref "LED51") (pin "4") (pinfunction "GND_4") (pintype "unspecified"))
      (node (ref "LED52") (pin "4") (pinfunction "GND_4") (pintype "unspecified"))
      (node (ref "LED53") (pin "4") (pinfunction "GND_4") (pintype "unspecified"))
      (node (ref "LED54") (pin "4") (pinfunction "GND_4") (pintype "unspecified"))
      (node (ref "LED55") (pin "4") (pinfunction "GND_4") (pintype "unspecified"))
      (node (ref "LED56") (pin "4") (pinfunction "GND_4") (pintype "unspecified"))
      (node (ref "LED57") (pin "4") (pinfunction "GND_4") (pintype "unspecified"))
      (node (ref "LED58") (pin "4") (pinfunction "GND_4") (pintype "unspecified"))
      (node (ref "LED59") (pin "4") (pinfunction "GND_4") (pintype "unspecified"))
      (node (ref "LED6") (pin "4") (pinfunction "GND_4") (pintype "unspecified"))
      (node (ref "LED60") (pin "4") (pinfunction "GND_4") (pintype "unspecified"))
      (node (ref "LED61") (pin "4") (pinfunction "GND_4") (pintype "unspecified"))
      (node (ref "LED62") (pin "4") (pinfunction "GND_4") (pintype "unspecified"))
      (node (ref "LED63") (pin "4") (pinfunction "GND_4") (pintype "unspecified"))
      (node (ref "LED64") (pin "4") (pinfunction "GND_4") (pintype "unspecified"))
      (node (ref "LED65") (pin "4") (pinfunction "GND_4") (pintype "unspecified"))
      (node (ref "LED66") (pin "4") (pinfunction "GND_4") (pintype "unspecified"))
      (node (ref "LED67") (pin "4") (pinfunction "GND_4") (pintype "unspecified"))
      (node (ref "LED68") (pin "4") (pinfunction "GND_4") (pintype "unspecified"))
      (node (ref "LED69") (pin "4") (pinfunction "GND_4") (pintype "unspecified"))
      (node (ref "LED7") (pin "4") (pinfunction "GND_4") (pintype "unspecified"))
      (node (ref "LED70") (pin "4") (pinfunction "GND_4") (pintype "unspecified"))
      (node (ref "LED71") (pin "4") (pinfunction "GND_4") (pintype "unspecified"))
      (node (ref "LED72") (pin "4") (pinfunction "GND_4") (pintype "unspecified"))
      (node (ref "LED73") (pin "4") (pinfunction "GND_4") (pintype "unspecified"))
      (node (ref "LED74") (pin "4") (pinfunction "GND_4") (pintype "unspecified"))
      (node (ref "LED75") (pin "4") (pinfunction "GND_4") (pintype "unspecified"))
      (node (ref "LED76") (pin "4") (pinfunction "GND_4") (pintype "unspecified"))
      (node (ref "LED77") (pin "4") (pinfunction "GND_4") (pintype "unspecified"))
      (node (ref "LED78") (pin "4") (pinfunction "GND_4") (pintype "unspecified"))
      (node (ref "LED79") (pin "4") (pinfunction "GND_4") (pintype "unspecified"))
      (node (ref "LED8") (pin "4") (pinfunction "GND_4") (pintype "unspecified"))
      (node (ref "LED80") (pin "4") (pinfunction "GND_4") (pintype "unspecified"))
      (node (ref "LED81") (pin "4") (pinfunction "GND_4") (pintype "unspecified"))
      (node (ref "LED82") (pin "4") (pinfunction "GND_4") (pintype "unspecified"))
      (node (ref "LED83") (pin "4") (pinfunction "GND_4") (pintype "unspecified"))
      (node (ref "LED84") (pin "4") (pinfunction "GND_4") (pintype "unspecified"))
      (node (ref "LED85") (pin "4") (pinfunction "GND_4") (pintype "unspecified"))
      (node (ref "LED86") (pin "4") (pinfunction "GND_4") (pintype "unspecified"))
      (node (ref "LED87") (pin "4") (pinfunction "GND_4") (pintype "unspecified"))
      (node (ref "LED88") (pin "4") (pinfunction "GND_4") (pintype "unspecified"))
      (node (ref "LED89") (pin "4") (pinfunction "GND_4") (pintype "unspecified"))
      (node (ref "LED9") (pin "4") (pinfunction "GND_4") (pintype "unspecified"))
      (node (ref "LED90") (pin "4") (pinfunction "GND_4") (pintype "unspecified"))
      (node (ref "LED91") (pin "4") (pinfunction "GND_4") (pintype "unspecified"))
      (node (ref "LED92") (pin "4") (pinfunction "GND_4") (pintype "unspecified"))
      (node (ref "LED93") (pin "4") (pinfunction "GND_4") (pintype "unspecified"))
      (node (ref "LED94") (pin "4") (pinfunction "GND_4") (pintype "unspecified"))
      (node (ref "LED95") (pin "4") (pinfunction "GND_4") (pintype "unspecified"))
      (node (ref "LED96") (pin "4") (pinfunction "GND_4") (pintype "unspecified"))
      (node (ref "LED97") (pin "4") (pinfunction "GND_4") (pintype "unspecified"))
      (node (ref "LED98") (pin "4") (pinfunction "GND_4") (pintype "unspecified"))
      (node (ref "LED99") (pin "4") (pinfunction "GND_4") (pintype "unspecified"))
      (node (ref "R10") (pin "2") (pinfunction "2_2") (pintype "input"))
      (node (ref "R5") (pin "1") (pinfunction "1_1") (pintype "input"))
      (node (ref "R9") (pin "1") (pinfunction "1_1") (pintype "input"))
      (node (ref "SC1") (pin "1") (pinfunction "1_1") (pintype "input"))
      (node (ref "SW1") (pin "1") (pinfunction "1_1") (pintype "unspecified"))
      (node (ref "U1") (pin "3") (pinfunction "GND_3") (pintype "unspecified"))
      (node (ref "U2") (pin "4") (pinfunction "VSS_4") (pintype "unspecified"))
      (node (ref "U3") (pin "1") (pinfunction "GND/ADJ_1") (pintype "unspecified"))
      (node (ref "U4") (pin "1") (pinfunction "GND_1") (pintype "unspecified"))
      (node (ref "U4") (pin "11") (pinfunction "GND_11") (pintype "unspecified"))
      (node (ref "U4") (pin "14") (pinfunction "GND_14") (pintype "unspecified"))
      (node (ref "U4") (pin "2") (pinfunction "GND_2") (pintype "unspecified"))
      (node (ref "U4") (pin "36") (pinfunction "GND_36") (pintype "unspecified"))
      (node (ref "U4") (pin "37") (pinfunction "GND_37") (pintype "unspecified"))
      (node (ref "U4") (pin "38") (pinfunction "GND_38") (pintype "unspecified"))
      (node (ref "U4") (pin "39") (pinfunction "GND_39") (pintype "unspecified"))
      (node (ref "U4") (pin "40") (pinfunction "GND_40") (pintype "unspecified"))
      (node (ref "U4") (pin "41") (pinfunction "GND_41") (pintype "unspecified"))
      (node (ref "U4") (pin "42") (pinfunction "GND_42") (pintype "unspecified"))
      (node (ref "U4") (pin "43") (pinfunction "GND_43") (pintype "unspecified"))
      (node (ref "U4") (pin "44") (pinfunction "GND_44") (pintype "unspecified"))
      (node (ref "U4") (pin "45") (pinfunction "GND_45") (pintype "unspecified"))
      (node (ref "U4") (pin "46") (pinfunction "GND_46") (pintype "unspecified"))
      (node (ref "U4") (pin "47") (pinfunction "GND_47") (pintype "unspecified"))
      (node (ref "U4") (pin "48") (pinfunction "GND_48") (pintype "unspecified"))
      (node (ref "U4") (pin "49") (pinfunction "GND_49") (pintype "unspecified"))
      (node (ref "U4") (pin "50") (pinfunction "GND_50") (pintype "unspecified"))
      (node (ref "U4") (pin "51") (pinfunction "GND_51") (pintype "unspecified"))
      (node (ref "U4") (pin "52") (pinfunction "GND_52") (pintype "unspecified"))
      (node (ref "U4") (pin "53") (pinfunction "GND_53") (pintype "unspecified"))
      (node (ref "USBC1") (pin "A1") (pinfunction "GND_A1") (pintype "unspecified"))
      (node (ref "USBC1") (pin "A12") (pinfunction "GND_A12") (pintype "unspecified"))
    )
    (net (code "8") (name "IO0_RTC_INT_A3") (class "Default")
      (node (ref "U2") (pin "3") (pinfunction "INT#_3") (pintype "unspecified"))
      (node (ref "U4") (pin "12") (pinfunction "IO0_12") (pintype "unspecified"))
    )
    (net (code "9") (name "IO1_ADC_A2") (class "Default")
      (node (ref "C2") (pin "2") (pinfunction "2_2") (pintype "unspecified"))
      (node (ref "Q1") (pin "2") (pinfunction "E1_2") (pintype "unspecified"))
      (node (ref "R5") (pin "2") (pinfunction "2_2") (pintype "input"))
      (node (ref "U4") (pin "13") (pinfunction "IO1_13") (pintype "unspecified"))
    )
    (net (code "10") (name "IO2_LEDS_3V3") (class "Default")
      (node (ref "R7") (pin "2") (pinfunction "2_2") (pintype "input"))
      (node (ref "U1") (pin "2") (pinfunction "A_2") (pintype "unspecified"))
      (node (ref "U4") (pin "5") (pinfunction "IO2_5") (pintype "unspecified"))
    )
    (net (code "11") (name "IO3_PRESS_A1") (class "Default")
      (node (ref "JOY1") (pin "2") (pinfunction "2_2") (pintype "unspecified"))
      (node (ref "U4") (pin "6") (pinfunction "IO3_6") (pintype "unspecified"))
    )
    (net (code "12") (name "IO4_LEFT") (class "Default")
      (node (ref "JOY1") (pin "4") (pinfunction "4_4") (pintype "unspecified"))
      (node (ref "U4") (pin "18") (pinfunction "IO4_18") (pintype "unspecified"))
    )
    (net (code "13") (name "IO5_SDA") (class "Default")
      (node (ref "CN1") (pin "3") (pinfunction "3_3") (pintype "unspecified"))
      (node (ref "H1") (pin "7") (pinfunction "7_7") (pintype "unspecified"))
      (node (ref "R1") (pin "2") (pinfunction "2_2") (pintype "input"))
      (node (ref "U2") (pin "5") (pinfunction "SDA_5") (pintype "unspecified"))
      (node (ref "U4") (pin "19") (pinfunction "IO5_19") (pintype "unspecified"))
    )
    (net (code "14") (name "IO6_SCL") (class "Default")
      (node (ref "CN1") (pin "4") (pinfunction "4_4") (pintype "unspecified"))
      (node (ref "H1") (pin "8") (pinfunction "8_8") (pintype "unspecified"))
      (node (ref "R2") (pin "2") (pinfunction "2_2") (pintype "input"))
      (node (ref "U2") (pin "6") (pinfunction "SCL_6") (pintype "unspecified"))
      (node (ref "U4") (pin "20") (pinfunction "IO6_20") (pintype "unspecified"))
    )
    (net (code "15") (name "IO7_DOWN") (class "Default")
      (node (ref "JOY1") (pin "1") (pinfunction "1_1") (pintype "unspecified"))
      (node (ref "U4") (pin "21") (pinfunction "IO7_21") (pintype "unspecified"))
    )
    (net (code "16") (name "IO8") (class "Default")
      (node (ref "H1") (pin "4") (pinfunction "4_4") (pintype "unspecified"))
      (node (ref "R8") (pin "2") (pinfunction "2_2") (pintype "input"))
      (node (ref "U4") (pin "22") (pinfunction "IO8_22") (pintype "unspecified"))
    )
    (net (code "17") (name "IO9_RIGHT_BOOT") (class "Default")
      (node (ref "JOY1") (pin "3") (pinfunction "3_3") (pintype "unspecified"))
      (node (ref "U4") (pin "23") (pinfunction "IO9_23") (pintype "unspecified"))
    )
    (net (code "18") (name "IO10_UP") (class "Default")
      (node (ref "JOY1") (pin "6") (pinfunction "6_6") (pintype "unspecified"))
      (node (ref "U4") (pin "16") (pinfunction "IO10_16") (pintype "unspecified"))
    )
    (net (code "19") (name "IO20_RXD") (class "Default")
      (node (ref "H1") (pin "5") (pinfunction "5_5") (pintype "unspecified"))
      (node (ref "U4") (pin "30") (pinfunction "RXD0_30") (pintype "unspecified"))
    )
    (net (code "20") (name "IO21_TXD") (class "Default")
      (node (ref "H1") (pin "6") (pinfunction "6_6") (pintype "unspecified"))
      (node (ref "R3") (pin "2") (pinfunction "2_2") (pintype "input"))
    )
    (net (code "21") (name "LEDS_DIN_5V") (class "Default")
      (node (ref "LED1") (pin "1") (pinfunction "DIN_1") (pintype "unspecified"))
      (node (ref "R4") (pin "2") (pinfunction "2_2") (pintype "input"))
    )
    (net (code "22") (name "Net-(D5--)") (class "Default")
      (node (ref "D5") (pin "1") (pinfunction "-_1") (pintype "unspecified"))
      (node (ref "SC1") (pin "2") (pinfunction "2_2") (pintype "input"))
      (node (ref "U2") (pin "8") (pinfunction "VDD_8") (pintype "unspecified"))
    )
    (net (code "23") (name "Net-(LED1-DO)") (class "Default")
      (node (ref "LED1") (pin "3") (pinfunction "DO_3") (pintype "unspecified"))
      (node (ref "LED2") (pin "1") (pinfunction "DIN_1") (pintype "unspecified"))
    )
    (net (code "24") (name "Net-(LED2-DO)") (class "Default")
      (node (ref "LED2") (pin "3") (pinfunction "DO_3") (pintype "unspecified"))
      (node (ref "LED3") (pin "1") (pinfunction "DIN_1") (pintype "unspecified"))
    )
    (net (code "25") (name "Net-(LED3-DO)") (class "Default")
      (node (ref "LED3") (pin "3") (pinfunction "DO_3") (pintype "unspecified"))
      (node (ref "LED4") (pin "1") (pinfunction "DIN_1") (pintype "unspecified"))
    )
    (net (code "26") (name "Net-(LED4-DO)") (class "Default")
      (node (ref "LED4") (pin "3") (pinfunction "DO_3") (pintype "unspecified"))
      (node (ref "LED5") (pin "1") (pinfunction "DIN_1") (pintype "unspecified"))
    )
    (net (code "27") (name "Net-(LED5-DO)") (class "Default")
      (node (ref "LED5") (pin "3") (pinfunction "DO_3") (pintype "unspecified"))
      (node (ref "LED6") (pin "1") (pinfunction "DIN_1") (pintype "unspecified"))
    )
    (net (code "28") (name "Net-(LED6-DO)") (class "Default")
      (node (ref "LED6") (pin "3") (pinfunction "DO_3") (pintype "unspecified"))
      (node (ref "LED7") (pin "1") (pinfunction "DIN_1") (pintype "unspecified"))
    )
    (net (code "29") (name "Net-(LED7-DO)") (class "Default")
      (node (ref "LED7") (pin "3") (pinfunction "DO_3") (pintype "unspecified"))
      (node (ref "LED8") (pin "1") (pinfunction "DIN_1") (pintype "unspecified"))
    )
    (net (code "30") (name "Net-(LED8-DO)") (class "Default")
      (node (ref "LED8") (pin "3") (pinfunction "DO_3") (pintype "unspecified"))
      (node (ref "LED9") (pin "1") (pinfunction "DIN_1") (pintype "unspecified"))
    )
    (net (code "31") (name "Net-(LED10-DIN)") (class "Default")
      (node (ref "LED10") (pin "1") (pinfunction "DIN_1") (pintype "unspecified"))
      (node (ref "LED9") (pin "3") (pinfunction "DO_3") (pintype "unspecified"))
    )
    (net (code "32") (name "Net-(LED10-DO)") (class "Default")
      (node (ref "LED10") (pin "3") (pinfunction "DO_3") (pintype "unspecified"))
      (node (ref "LED11") (pin "1") (pinfunction "DIN_1") (pintype "unspecified"))
    )
    (net (code "33") (name "Net-(LED11-DO)") (class "Default")
      (node (ref "LED11") (pin "3") (pinfunction "DO_3") (pintype "unspecified"))
      (node (ref "LED12") (pin "1") (pinfunction "DIN_1") (pintype "unspecified"))
    )
    (net (code "34") (name "Net-(LED12-DO)") (class "Default")
      (node (ref "LED12") (pin "3") (pinfunction "DO_3") (pintype "unspecified"))
      (node (ref "LED13") (pin "1") (pinfunction "DIN_1") (pintype "unspecified"))
    )
    (net (code "35") (name "Net-(LED13-DO)") (class "Default")
      (node (ref "LED13") (pin "3") (pinfunction "DO_3") (pintype "unspecified"))
      (node (ref "LED14") (pin "1") (pinfunction "DIN_1") (pintype "unspecified"))
    )
    (net (code "36") (name "Net-(LED14-DO)") (class "Default")
      (node (ref "LED14") (pin "3") (pinfunction "DO_3") (pintype "unspecified"))
      (node (ref "LED15") (pin "1") (pinfunction "DIN_1") (pintype "unspecified"))
    )
    (net (code "37") (name "Net-(LED15-DO)") (class "Default")
      (node (ref "LED15") (pin "3") (pinfunction "DO_3") (pintype "unspecified"))
      (node (ref "LED16") (pin "1") (pinfunction "DIN_1") (pintype "unspecified"))
    )
    (net (code "38") (name "Net-(LED16-DO)") (class "Default")
      (node (ref "LED16") (pin "3") (pinfunction "DO_3") (pintype "unspecified"))
      (node (ref "LED17") (pin "1") (pinfunction "DIN_1") (pintype "unspecified"))
    )
    (net (code "39") (name "Net-(LED17-DO)") (class "Default")
      (node (ref "LED17") (pin "3") (pinfunction "DO_3") (pintype "unspecified"))
      (node (ref "LED18") (pin "1") (pinfunction "DIN_1") (pintype "unspecified"))
    )
    (net (code "40") (name "Net-(LED18-DO)") (class "Default")
      (node (ref "LED18") (pin "3") (pinfunction "DO_3") (pintype "unspecified"))
      (node (ref "LED19") (pin "1") (pinfunction "DIN_1") (pintype "unspecified"))
    )
    (net (code "41") (name "Net-(LED19-DO)") (class "Default")
      (node (ref "LED19") (pin "3") (pinfunction "DO_3") (pintype "unspecified"))
      (node (ref "LED20") (pin "1") (pinfunction "DIN_1") (pintype "unspecified"))
    )
    (net (code "42") (name "Net-(LED20-DO)") (class "Default")
      (node (ref "LED20") (pin "3") (pinfunction "DO_3") (pintype "unspecified"))
      (node (ref "LED21") (pin "1") (pinfunction "DIN_1") (pintype "unspecified"))
    )
    (net (code "43") (name "Net-(LED21-DO)") (class "Default")
      (node (ref "LED21") (pin "3") (pinfunction "DO_3") (pintype "unspecified"))
      (node (ref "LED22") (pin "1") (pinfunction "DIN_1") (pintype "unspecified"))
    )
    (net (code "44") (name "Net-(LED22-DO)") (class "Default")
      (node (ref "LED22") (pin "3") (pinfunction "DO_3") (pintype "unspecified"))
      (node (ref "LED23") (pin "1") (pinfunction "DIN_1") (pintype "unspecified"))
    )
    (net (code "45") (name "Net-(LED23-DO)") (class "Default")
      (node (ref "LED23") (pin "3") (pinfunction "DO_3") (pintype "unspecified"))
      (node (ref "LED24") (pin "1") (pinfunction "DIN_1") (pintype "unspecified"))
    )
    (net (code "46") (name "Net-(LED24-DO)") (class "Default")
      (node (ref "LED24") (pin "3") (pinfunction "DO_3") (pintype "unspecified"))
      (node (ref "LED25") (pin "1") (pinfunction "DIN_1") (pintype "unspecified"))
    )
    (net (code "47") (name "Net-(LED25-DO)") (class "Default")
      (node (ref "LED25") (pin "3") (pinfunction "DO_3") (pintype "unspecified"))
      (node (ref "LED26") (pin "1") (pinfunction "DIN_1") (pintype "unspecified"))
    )
    (net (code "48") (name "Net-(LED26-DO)") (class "Default")
      (node (ref "LED26") (pin "3") (pinfunction "DO_3") (pintype "unspecified"))
      (node (ref "LED27") (pin "1") (pinfunction "DIN_1") (pintype "unspecified"))
    )
    (net (code "49") (name "Net-(LED27-DO)") (class "Default")
      (node (ref "LED27") (pin "3") (pinfunction "DO_3") (pintype "unspecified"))
      (node (ref "LED28") (pin "1") (pinfunction "DIN_1") (pintype "unspecified"))
    )
    (net (code "50") (name "Net-(LED28-DO)") (class "Default")
      (node (ref "LED28") (pin "3") (pinfunction "DO_3") (pintype "unspecified"))
      (node (ref "LED29") (pin "1") (pinfunction "DIN_1") (pintype "unspecified"))
    )
    (net (code "51") (name "Net-(LED29-DO)") (class "Default")
      (node (ref "LED29") (pin "3") (pinfunction "DO_3") (pintype "unspecified"))
      (node (ref "LED30") (pin "1") (pinfunction "DIN_1") (pintype "unspecified"))
    )
    (net (code "52") (name "Net-(LED30-DO)") (class "Default")
      (node (ref "LED30") (pin "3") (pinfunction "DO_3") (pintype "unspecified"))
      (node (ref "LED31") (pin "1") (pinfunction "DIN_1") (pintype "unspecified"))
    )
    (net (code "53") (name "Net-(LED31-DO)") (class "Default")
      (node (ref "LED31") (pin "3") (pinfunction "DO_3") (pintype "unspecified"))
      (node (ref "LED32") (pin "1") (pinfunction "DIN_1") (pintype "unspecified"))
    )
    (net (code "54") (name "Net-(LED32-DO)") (class "Default")
      (node (ref "LED32") (pin "3") (pinfunction "DO_3") (pintype "unspecified"))
      (node (ref "LED33") (pin "1") (pinfunction "DIN_1") (pintype "unspecified"))
    )
    (net (code "55") (name "Net-(LED33-DO)") (class "Default")
      (node (ref "LED33") (pin "3") (pinfunction "DO_3") (pintype "unspecified"))
      (node (ref "LED34") (pin "1") (pinfunction "DIN_1") (pintype "unspecified"))
    )
    (net (code "56") (name "Net-(LED34-DO)") (class "Default")
      (node (ref "LED34") (pin "3") (pinfunction "DO_3") (pintype "unspecified"))
      (node (ref "LED35") (pin "1") (pinfunction "DIN_1") (pintype "unspecified"))
    )
    (net (code "57") (name "Net-(LED35-DO)") (class "Default")
      (node (ref "LED35") (pin "3") (pinfunction "DO_3") (pintype "unspecified"))
      (node (ref "LED36") (pin "1") (pinfunction "DIN_1") (pintype "unspecified"))
    )
    (net (code "58") (name "Net-(LED36-DO)") (class "Default")
      (node (ref "LED36") (pin "3") (pinfunction "DO_3") (pintype "unspecified"))
      (node (ref "LED37") (pin "1") (pinfunction "DIN_1") (pintype "unspecified"))
    )
    (net (code "59") (name "Net-(LED37-DO)") (class "Default")
      (node (ref "LED37") (pin "3") (pinfunction "DO_3") (pintype "unspecified"))
      (node (ref "LED38") (pin "1") (pinfunction "DIN_1") (pintype "unspecified"))
    )
    (net (code "60") (name "Net-(LED38-DO)") (class "Default")
      (node (ref "LED38") (pin "3") (pinfunction "DO_3") (pintype "unspecified"))
      (node (ref "LED39") (pin "1") (pinfunction "DIN_1") (pintype "unspecified"))
    )
    (net (code "61") (name "Net-(LED39-DO)") (class "Default")
      (node (ref "LED39") (pin "3") (pinfunction "DO_3") (pintype "unspecified"))
      (node (ref "LED40") (pin "1") (pinfunction "DIN_1") (pintype "unspecified"))
    )
    (net (code "62") (name "Net-(LED40-DO)") (class "Default")
      (node (ref "LED40") (pin "3") (pinfunction "DO_3") (pintype "unspecified"))
      (node (ref "LED41") (pin "1") (pinfunction "DIN_1") (pintype "unspecified"))
    )
    (net (code "63") (name "Net-(LED41-DO)") (class "Default")
      (node (ref "LED41") (pin "3") (pinfunction "DO_3") (pintype "unspecified"))
      (node (ref "LED42") (pin "1") (pinfunction "DIN_1") (pintype "unspecified"))
    )
    (net (code "64") (name "Net-(LED42-DO)") (class "Default")
      (node (ref "LED42") (pin "3") (pinfunction "DO_3") (pintype "unspecified"))
      (node (ref "LED43") (pin "1") (pinfunction "DIN_1") (pintype "unspecified"))
    )
    (net (code "65") (name "Net-(LED43-DO)") (class "Default")
      (node (ref "LED43") (pin "3") (pinfunction "DO_3") (pintype "unspecified"))
      (node (ref "LED44") (pin "1") (pinfunction "DIN_1") (pintype "unspecified"))
    )
    (net (code "66") (name "Net-(LED44-DO)") (class "Default")
      (node (ref "LED44") (pin "3") (pinfunction "DO_3") (pintype "unspecified"))
      (node (ref "LED45") (pin "1") (pinfunction "DIN_1") (pintype "unspecified"))
    )
    (net (code "67") (name "Net-(LED45-DO)") (class "Default")
      (node (ref "LED45") (pin "3") (pinfunction "DO_3") (pintype "unspecified"))
      (node (ref "LED46") (pin "1") (pinfunction "DIN_1") (pintype "unspecified"))
    )
    (net (code "68") (name "Net-(LED46-DO)") (class "Default")
      (node (ref "LED46") (pin "3") (pinfunction "DO_3") (pintype "unspecified"))
      (node (ref "LED47") (pin "1") (pinfunction "DIN_1") (pintype "unspecified"))
    )
    (net (code "69") (name "Net-(LED47-DO)") (class "Default")
      (node (ref "LED47") (pin "3") (pinfunction "DO_3") (pintype "unspecified"))
      (node (ref "LED48") (pin "1") (pinfunction "DIN_1") (pintype "unspecified"))
    )
    (net (code "70") (name "Net-(LED48-DO)") (class "Default")
      (node (ref "LED48") (pin "3") (pinfunction "DO_3") (pintype "unspecified"))
      (node (ref "LED49") (pin "1") (pinfunction "DIN_1") (pintype "unspecified"))
    )
    (net (code "71") (name "Net-(LED49-DO)") (class "Default")
      (node (ref "LED49") (pin "3") (pinfunction "DO_3") (pintype "unspecified"))
      (node (ref "LED50") (pin "1") (pinfunction "DIN_1") (pintype "unspecified"))
    )
    (net (code "72") (name "Net-(LED50-DO)") (class "Default")
      (node (ref "LED50") (pin "3") (pinfunction "DO_3") (pintype "unspecified"))
      (node (ref "LED51") (pin "1") (pinfunction "DIN_1") (pintype "unspecified"))
    )
    (net (code "73") (name "Net-(LED51-DO)") (class "Default")
      (node (ref "LED51") (pin "3") (pinfunction "DO_3") (pintype "unspecified"))
      (node (ref "LED52") (pin "1") (pinfunction "DIN_1") (pintype "unspecified"))
    )
    (net (code "74") (name "Net-(LED52-DO)") (class "Default")
      (node (ref "LED52") (pin "3") (pinfunction "DO_3") (pintype "unspecified"))
      (node (ref "LED53") (pin "1") (pinfunction "DIN_1") (pintype "unspecified"))
    )
    (net (code "75") (name "Net-(LED53-DO)") (class "Default")
      (node (ref "LED53") (pin "3") (pinfunction "DO_3") (pintype "unspecified"))
      (node (ref "LED54") (pin "1") (pinfunction "DIN_1") (pintype "unspecified"))
    )
    (net (code "76") (name "Net-(LED54-DO)") (class "Default")
      (node (ref "LED54") (pin "3") (pinfunction "DO_3") (pintype "unspecified"))
      (node (ref "LED55") (pin "1") (pinfunction "DIN_1") (pintype "unspecified"))
    )
    (net (code "77") (name "Net-(LED55-DO)") (class "Default")
      (node (ref "LED55") (pin "3") (pinfunction "DO_3") (pintype "unspecified"))
      (node (ref "LED56") (pin "1") (pinfunction "DIN_1") (pintype "unspecified"))
    )
    (net (code "78") (name "Net-(LED56-DO)") (class "Default")
      (node (ref "LED56") (pin "3") (pinfunction "DO_3") (pintype "unspecified"))
      (node (ref "LED57") (pin "1") (pinfunction "DIN_1") (pintype "unspecified"))
    )
    (net (code "79") (name "Net-(LED57-DO)") (class "Default")
      (node (ref "LED57") (pin "3") (pinfunction "DO_3") (pintype "unspecified"))
      (node (ref "LED58") (pin "1") (pinfunction "DIN_1") (pintype "unspecified"))
    )
    (net (code "80") (name "Net-(LED58-DO)") (class "Default")
      (node (ref "LED58") (pin "3") (pinfunction "DO_3") (pintype "unspecified"))
      (node (ref "LED59") (pin "1") (pinfunction "DIN_1") (pintype "unspecified"))
    )
    (net (code "81") (name "Net-(LED59-DO)") (class "Default")
      (node (ref "LED59") (pin "3") (pinfunction "DO_3") (pintype "unspecified"))
      (node (ref "LED60") (pin "1") (pinfunction "DIN_1") (pintype "unspecified"))
    )
    (net (code "82") (name "Net-(LED60-DO)") (class "Default")
      (node (ref "LED60") (pin "3") (pinfunction "DO_3") (pintype "unspecified"))
      (node (ref "LED61") (pin "1") (pinfunction "DIN_1") (pintype "unspecified"))
    )
    (net (code "83") (name "Net-(LED61-DO)") (class "Default")
      (node (ref "LED61") (pin "3") (pinfunction "DO_3") (pintype "unspecified"))
      (node (ref "LED62") (pin "1") (pinfunction "DIN_1") (pintype "unspecified"))
    )
    (net (code "84") (name "Net-(LED62-DO)") (class "Default")
      (node (ref "LED62") (pin "3") (pinfunction "DO_3") (pintype "unspecified"))
      (node (ref "LED63") (pin "1") (pinfunction "DIN_1") (pintype "unspecified"))
    )
    (net (code "85") (name "Net-(LED63-DO)") (class "Default")
      (node (ref "LED63") (pin "3") (pinfunction "DO_3") (pintype "unspecified"))
      (node (ref "LED64") (pin "1") (pinfunction "DIN_1") (pintype "unspecified"))
    )
    (net (code "86") (name "Net-(LED64-DO)") (class "Default")
      (node (ref "LED64") (pin "3") (pinfunction "DO_3") (pintype "unspecified"))
      (node (ref "LED65") (pin "1") (pinfunction "DIN_1") (pintype "unspecified"))
    )
    (net (code "87") (name "Net-(LED65-DO)") (class "Default")
      (node (ref "LED65") (pin "3") (pinfunction "DO_3") (pintype "unspecified"))
      (node (ref "LED66") (pin "1") (pinfunction "DIN_1") (pintype "unspecified"))
    )
    (net (code "88") (name "Net-(LED66-DO)") (class "Default")
      (node (ref "LED66") (pin "3") (pinfunction "DO_3") (pintype "unspecified"))
      (node (ref "LED67") (pin "1") (pinfunction "DIN_1") (pintype "unspecified"))
    )
    (net (code "89") (name "Net-(LED67-DO)") (class "Default")
      (node (ref "LED67") (pin "3") (pinfunction "DO_3") (pintype "unspecified"))
      (node (ref "LED68") (pin "1") (pinfunction "DIN_1") (pintype "unspecified"))
    )
    (net (code "90") (name "Net-(LED68-DO)") (class "Default")
      (node (ref "LED68") (pin "3") (pinfunction "DO_3") (pintype "unspecified"))
      (node (ref "LED69") (pin "1") (pinfunction "DIN_1") (pintype "unspecified"))
    )
    (net (code "91") (name "Net-(LED69-DO)") (class "Default")
      (node (ref "LED69") (pin "3") (pinfunction "DO_3") (pintype "unspecified"))
      (node (ref "LED70") (pin "1") (pinfunction "DIN_1") (pintype "unspecified"))
    )
    (net (code "92") (name "Net-(LED70-DO)") (class "Default")
      (node (ref "LED70") (pin "3") (pinfunction "DO_3") (pintype "unspecified"))
      (node (ref "LED71") (pin "1") (pinfunction "DIN_1") (pintype "unspecified"))
    )
    (net (code "93") (name "Net-(LED71-DO)") (class "Default")
      (node (ref "LED71") (pin "3") (pinfunction "DO_3") (pintype "unspecified"))
      (node (ref "LED72") (pin "1") (pinfunction "DIN_1") (pintype "unspecified"))
    )
    (net (code "94") (name "Net-(LED72-DO)") (class "Default")
      (node (ref "LED72") (pin "3") (pinfunction "DO_3") (pintype "unspecified"))
      (node (ref "LED73") (pin "1") (pinfunction "DIN_1") (pintype "unspecified"))
    )
    (net (code "95") (name "Net-(LED73-DO)") (class "Default")
      (node (ref "LED73") (pin "3") (pinfunction "DO_3") (pintype "unspecified"))
      (node (ref "LED74") (pin "1") (pinfunction "DIN_1") (pintype "unspecified"))
    )
    (net (code "96") (name "Net-(LED74-DO)") (class "Default")
      (node (ref "LED74") (pin "3") (pinfunction "DO_3") (pintype "unspecified"))
      (node (ref "LED75") (pin "1") (pinfunction "DIN_1") (pintype "unspecified"))
    )
    (net (code "97") (name "Net-(LED75-DO)") (class "Default")
      (node (ref "LED75") (pin "3") (pinfunction "DO_3") (pintype "unspecified"))
      (node (ref "LED76") (pin "1") (pinfunction "DIN_1") (pintype "unspecified"))
    )
    (net (code "98") (name "Net-(LED76-DO)") (class "Default")
      (node (ref "LED76") (pin "3") (pinfunction "DO_3") (pintype "unspecified"))
      (node (ref "LED77") (pin "1") (pinfunction "DIN_1") (pintype "unspecified"))
    )
    (net (code "99") (name "Net-(LED77-DO)") (class "Default")
      (node (ref "LED77") (pin "3") (pinfunction "DO_3") (pintype "unspecified"))
      (node (ref "LED78") (pin "1") (pinfunction "DIN_1") (pintype "unspecified"))
    )
    (net (code "100") (name "Net-(LED78-DO)") (class "Default")
      (node (ref "LED78") (pin "3") (pinfunction "DO_3") (pintype "unspecified"))
      (node (ref "LED79") (pin "1") (pinfunction "DIN_1") (pintype "unspecified"))
    )
    (net (code "101") (name "Net-(LED79-DO)") (class "Default")
      (node (ref "LED79") (pin "3") (pinfunction "DO_3") (pintype "unspecified"))
      (node (ref "LED80") (pin "1") (pinfunction "DIN_1") (pintype "unspecified"))
    )
    (net (code "102") (name "Net-(LED80-DO)") (class "Default")
      (node (ref "LED80") (pin "3") (pinfunction "DO_3") (pintype "unspecified"))
      (node (ref "LED81") (pin "1") (pinfunction "DIN_1") (pintype "unspecified"))
    )
    (net (code "103") (name "Net-(LED81-DO)") (class "Default")
      (node (ref "LED81") (pin "3") (pinfunction "DO_3") (pintype "unspecified"))
      (node (ref "LED82") (pin "1") (pinfunction "DIN_1") (pintype "unspecified"))
    )
    (net (code "104") (name "Net-(LED82-DO)") (class "Default")
      (node (ref "LED82") (pin "3") (pinfunction "DO_3") (pintype "unspecified"))
      (node (ref "LED83") (pin "1") (pinfunction "DIN_1") (pintype "unspecified"))
    )
    (net (code "105") (name "Net-(LED83-DO)") (class "Default")
      (node (ref "LED83") (pin "3") (pinfunction "DO_3") (pintype "unspecified"))
      (node (ref "LED84") (pin "1") (pinfunction "DIN_1") (pintype "unspecified"))
    )
    (net (code "106") (name "Net-(LED84-DO)") (class "Default")
      (node (ref "LED84") (pin "3") (pinfunction "DO_3") (pintype "unspecified"))
      (node (ref "LED85") (pin "1") (pinfunction "DIN_1") (pintype "unspecified"))
    )
    (net (code "107") (name "Net-(LED85-DO)") (class "Default")
      (node (ref "LED85") (pin "3") (pinfunction "DO_3") (pintype "unspecified"))
      (node (ref "LED86") (pin "1") (pinfunction "DIN_1") (pintype "unspecified"))
    )
    (net (code "108") (name "Net-(LED86-DO)") (class "Default")
      (node (ref "LED86") (pin "3") (pinfunction "DO_3") (pintype "unspecified"))
      (node (ref "LED87") (pin "1") (pinfunction "DIN_1") (pintype "unspecified"))
    )
    (net (code "109") (name "Net-(LED87-DO)") (class "Default")
      (node (ref "LED87") (pin "3") (pinfunction "DO_3") (pintype "unspecified"))
      (node (ref "LED88") (pin "1") (pinfunction "DIN_1") (pintype "unspecified"))
    )
    (net (code "110") (name "Net-(LED88-DO)") (class "Default")
      (node (ref "LED88") (pin "3") (pinfunction "DO_3") (pintype "unspecified"))
      (node (ref "LED89") (pin "1") (pinfunction "DIN_1") (pintype "unspecified"))
    )
    (net (code "111") (name "Net-(LED89-DO)") (class "Default")
      (node (ref "LED89") (pin "3") (pinfunction "DO_3") (pintype "unspecified"))
      (node (ref "LED90") (pin "1") (pinfunction "DIN_1") (pintype "unspecified"))
    )
    (net (code "112") (name "Net-(LED90-DO)") (class "Default")
      (node (ref "LED90") (pin "3") (pinfunction "DO_3") (pintype "unspecified"))
      (node (ref "LED91") (pin "1") (pinfunction "DIN_1") (pintype "unspecified"))
    )
    (net (code "113") (name "Net-(LED91-DO)") (class "Default")
      (node (ref "LED91") (pin "3") (pinfunction "DO_3") (pintype "unspecified"))
      (node (ref "LED92") (pin "1") (pinfunction "DIN_1") (pintype "unspecified"))
    )
    (net (code "114") (name "Net-(LED92-DO)") (class "Default")
      (node (ref "LED92") (pin "3") (pinfunction "DO_3") (pintype "unspecified"))
      (node (ref "LED93") (pin "1") (pinfunction "DIN_1") (pintype "unspecified"))
    )
    (net (code "115") (name "Net-(LED93-DO)") (class "Default")
      (node (ref "LED93") (pin "3") (pinfunction "DO_3") (pintype "unspecified"))
      (node (ref "LED94") (pin "1") (pinfunction "DIN_1") (pintype "unspecified"))
    )
    (net (code "116") (name "Net-(LED94-DO)") (class "Default")
      (node (ref "LED94") (pin "3") (pinfunction "DO_3") (pintype "unspecified"))
      (node (ref "LED95") (pin "1") (pinfunction "DIN_1") (pintype "unspecified"))
    )
    (net (code "117") (name "Net-(LED95-DO)") (class "Default")
      (node (ref "LED95") (pin "3") (pinfunction "DO_3") (pintype "unspecified"))
      (node (ref "LED96") (pin "1") (pinfunction "DIN_1") (pintype "unspecified"))
    )
    (net (code "118") (name "Net-(LED96-DO)") (class "Default")
      (node (ref "LED96") (pin "3") (pinfunction "DO_3") (pintype "unspecified"))
      (node (ref "LED97") (pin "1") (pinfunction "DIN_1") (pintype "unspecified"))
    )
    (net (code "119") (name "Net-(LED97-DO)") (class "Default")
      (node (ref "LED97") (pin "3") (pinfunction "DO_3") (pintype "unspecified"))
      (node (ref "LED98") (pin "1") (pinfunction "DIN_1") (pintype "unspecified"))
    )
    (net (code "120") (name "Net-(LED98-DO)") (class "Default")
      (node (ref "LED98") (pin "3") (pinfunction "DO_3") (pintype "unspecified"))
      (node (ref "LED99") (pin "1") (pinfunction "DIN_1") (pintype "unspecified"))
    )
    (net (code "121") (name "Net-(LED100-DIN)") (class "Default")
      (node (ref "LED100") (pin "1") (pinfunction "DIN_1") (pintype "unspecified"))
      (node (ref "LED99") (pin "3") (pinfunction "DO_3") (pintype "unspecified"))
    )
    (net (code "122") (name "Net-(LED100-DO)") (class "Default")
      (node (ref "LED100") (pin "3") (pinfunction "DO_3") (pintype "unspecified"))
      (node (ref "LED101") (pin "1") (pinfunction "DIN_1") (pintype "unspecified"))
    )
    (net (code "123") (name "Net-(LED101-DO)") (class "Default")
      (node (ref "LED101") (pin "3") (pinfunction "DO_3") (pintype "unspecified"))
      (node (ref "LED102") (pin "1") (pinfunction "DIN_1") (pintype "unspecified"))
    )
    (net (code "124") (name "Net-(LED102-DO)") (class "Default")
      (node (ref "LED102") (pin "3") (pinfunction "DO_3") (pintype "unspecified"))
      (node (ref "LED103") (pin "1") (pinfunction "DIN_1") (pintype "unspecified"))
    )
    (net (code "125") (name "Net-(LED103-DO)") (class "Default")
      (node (ref "LED103") (pin "3") (pinfunction "DO_3") (pintype "unspecified"))
      (node (ref "LED104") (pin "1") (pinfunction "DIN_1") (pintype "unspecified"))
    )
    (net (code "126") (name "Net-(LED104-DO)") (class "Default")
      (node (ref "LED104") (pin "3") (pinfunction "DO_3") (pintype "unspecified"))
      (node (ref "LED105") (pin "1") (pinfunction "DIN_1") (pintype "unspecified"))
    )
    (net (code "127") (name "Net-(LED105-DO)") (class "Default")
      (node (ref "LED105") (pin "3") (pinfunction "DO_3") (pintype "unspecified"))
      (node (ref "LED106") (pin "1") (pinfunction "DIN_1") (pintype "unspecified"))
    )
    (net (code "128") (name "Net-(LED106-DO)") (class "Default")
      (node (ref "LED106") (pin "3") (pinfunction "DO_3") (pintype "unspecified"))
      (node (ref "LED107") (pin "1") (pinfunction "DIN_1") (pintype "unspecified"))
    )
    (net (code "129") (name "Net-(LED107-DO)") (class "Default")
      (node (ref "LED107") (pin "3") (pinfunction "DO_3") (pintype "unspecified"))
      (node (ref "LED108") (pin "1") (pinfunction "DIN_1") (pintype "unspecified"))
    )
    (net (code "130") (name "Net-(LED108-DO)") (class "Default")
      (node (ref "LED108") (pin "3") (pinfunction "DO_3") (pintype "unspecified"))
      (node (ref "LED109") (pin "1") (pinfunction "DIN_1") (pintype "unspecified"))
    )
    (net (code "131") (name "Net-(LED109-DO)") (class "Default")
      (node (ref "LED109") (pin "3") (pinfunction "DO_3") (pintype "unspecified"))
      (node (ref "LED110") (pin "1") (pinfunction "DIN_1") (pintype "unspecified"))
    )
    (net (code "132") (name "Net-(LED110-DO)") (class "Default")
      (node (ref "LED110") (pin "3") (pinfunction "DO_3") (pintype "unspecified"))
      (node (ref "LED111") (pin "1") (pinfunction "DIN_1") (pintype "unspecified"))
    )
    (net (code "133") (name "Net-(LED111-DO)") (class "Default")
      (node (ref "LED111") (pin "3") (pinfunction "DO_3") (pintype "unspecified"))
      (node (ref "LED112") (pin "1") (pinfunction "DIN_1") (pintype "unspecified"))
    )
    (net (code "134") (name "Net-(LED112-DO)") (class "Default")
      (node (ref "LED112") (pin "3") (pinfunction "DO_3") (pintype "unspecified"))
      (node (ref "LED113") (pin "1") (pinfunction "DIN_1") (pintype "unspecified"))
    )
    (net (code "135") (name "Net-(LED113-DO)") (class "Default")
      (node (ref "LED113") (pin "3") (pinfunction "DO_3") (pintype "unspecified"))
      (node (ref "LED114") (pin "1") (pinfunction "DIN_1") (pintype "unspecified"))
    )
    (net (code "136") (name "Net-(LED114-DO)") (class "Default")
      (node (ref "LED114") (pin "3") (pinfunction "DO_3") (pintype "unspecified"))
      (node (ref "LED115") (pin "1") (pinfunction "DIN_1") (pintype "unspecified"))
    )
    (net (code "137") (name "Net-(LED115-DO)") (class "Default")
      (node (ref "LED115") (pin "3") (pinfunction "DO_3") (pintype "unspecified"))
      (node (ref "LED116") (pin "1") (pinfunction "DIN_1") (pintype "unspecified"))
    )
    (net (code "138") (name "Net-(LED116-DO)") (class "Default")
      (node (ref "LED116") (pin "3") (pinfunction "DO_3") (pintype "unspecified"))
      (node (ref "LED117") (pin "1") (pinfunction "DIN_1") (pintype "unspecified"))
    )
    (net (code "139") (name "Net-(LED117-DO)") (class "Default")
      (node (ref "LED117") (pin "3") (pinfunction "DO_3") (pintype "unspecified"))
      (node (ref "LED118") (pin "1") (pinfunction "DIN_1") (pintype "unspecified"))
    )
    (net (code "140") (name "Net-(LED118-DO)") (class "Default")
      (node (ref "LED118") (pin "3") (pinfunction "DO_3") (pintype "unspecified"))
      (node (ref "LED119") (pin "1") (pinfunction "DIN_1") (pintype "unspecified"))
    )
    (net (code "141") (name "Net-(LED119-DO)") (class "Default")
      (node (ref "LED119") (pin "3") (pinfunction "DO_3") (pintype "unspecified"))
      (node (ref "LED120") (pin "1") (pinfunction "DIN_1") (pintype "unspecified"))
    )
    (net (code "142") (name "Net-(LED120-DO)") (class "Default")
      (node (ref "LED120") (pin "3") (pinfunction "DO_3") (pintype "unspecified"))
      (node (ref "LED121") (pin "1") (pinfunction "DIN_1") (pintype "unspecified"))
    )
    (net (code "143") (name "Net-(LED121-DO)") (class "Default")
      (node (ref "LED121") (pin "3") (pinfunction "DO_3") (pintype "unspecified"))
      (node (ref "LED122") (pin "1") (pinfunction "DIN_1") (pintype "unspecified"))
    )
    (net (code "144") (name "Net-(LED122-DO)") (class "Default")
      (node (ref "LED122") (pin "3") (pinfunction "DO_3") (pintype "unspecified"))
      (node (ref "LED123") (pin "1") (pinfunction "DIN_1") (pintype "unspecified"))
    )
    (net (code "145") (name "Net-(LED123-DO)") (class "Default")
      (node (ref "LED123") (pin "3") (pinfunction "DO_3") (pintype "unspecified"))
      (node (ref "LED124") (pin "1") (pinfunction "DIN_1") (pintype "unspecified"))
    )
    (net (code "146") (name "Net-(LED124-DO)") (class "Default")
      (node (ref "LED124") (pin "3") (pinfunction "DO_3") (pintype "unspecified"))
      (node (ref "LED125") (pin "1") (pinfunction "DIN_1") (pintype "unspecified"))
    )
    (net (code "147") (name "Net-(LED125-DO)") (class "Default")
      (node (ref "LED125") (pin "3") (pinfunction "DO_3") (pintype "unspecified"))
      (node (ref "LED126") (pin "1") (pinfunction "DIN_1") (pintype "unspecified"))
    )
    (net (code "148") (name "Net-(LED126-DO)") (class "Default")
      (node (ref "LED126") (pin "3") (pinfunction "DO_3") (pintype "unspecified"))
      (node (ref "LED127") (pin "1") (pinfunction "DIN_1") (pintype "unspecified"))
    )
    (net (code "149") (name "Net-(LED127-DO)") (class "Default")
      (node (ref "LED127") (pin "3") (pinfunction "DO_3") (pintype "unspecified"))
      (node (ref "LED128") (pin "1") (pinfunction "DIN_1") (pintype "unspecified"))
    )
    (net (code "150") (name "Net-(LED128-DO)") (class "Default")
      (node (ref "LED128") (pin "3") (pinfunction "DO_3") (pintype "unspecified"))
      (node (ref "LED129") (pin "1") (pinfunction "DIN_1") (pintype "unspecified"))
    )
    (net (code "151") (name "Net-(LED129-DO)") (class "Default")
      (node (ref "LED129") (pin "3") (pinfunction "DO_3") (pintype "unspecified"))
      (node (ref "LED130") (pin "1") (pinfunction "DIN_1") (pintype "unspecified"))
    )
    (net (code "152") (name "Net-(LED130-DO)") (class "Default")
      (node (ref "LED130") (pin "3") (pinfunction "DO_3") (pintype "unspecified"))
      (node (ref "LED131") (pin "1") (pinfunction "DIN_1") (pintype "unspecified"))
    )
    (net (code "153") (name "Net-(LED131-DO)") (class "Default")
      (node (ref "LED131") (pin "3") (pinfunction "DO_3") (pintype "unspecified"))
      (node (ref "LED132") (pin "1") (pinfunction "DIN_1") (pintype "unspecified"))
    )
    (net (code "154") (name "Net-(LED132-DO)") (class "Default")
      (node (ref "LED132") (pin "3") (pinfunction "DO_3") (pintype "unspecified"))
      (node (ref "LED133") (pin "1") (pinfunction "DIN_1") (pintype "unspecified"))
    )
    (net (code "155") (name "Net-(LED133-DO)") (class "Default")
      (node (ref "LED133") (pin "3") (pinfunction "DO_3") (pintype "unspecified"))
      (node (ref "LED134") (pin "1") (pinfunction "DIN_1") (pintype "unspecified"))
    )
    (net (code "156") (name "Net-(LED134-DO)") (class "Default")
      (node (ref "LED134") (pin "3") (pinfunction "DO_3") (pintype "unspecified"))
      (node (ref "LED135") (pin "1") (pinfunction "DIN_1") (pintype "unspecified"))
    )
    (net (code "157") (name "Net-(LED135-DO)") (class "Default")
      (node (ref "LED135") (pin "3") (pinfunction "DO_3") (pintype "unspecified"))
      (node (ref "LED136") (pin "1") (pinfunction "DIN_1") (pintype "unspecified"))
    )
    (net (code "158") (name "Net-(LED136-DO)") (class "Default")
      (node (ref "LED136") (pin "3") (pinfunction "DO_3") (pintype "unspecified"))
      (node (ref "LED137") (pin "1") (pinfunction "DIN_1") (pintype "unspecified"))
    )
    (net (code "159") (name "Net-(LED137-DO)") (class "Default")
      (node (ref "LED137") (pin "3") (pinfunction "DO_3") (pintype "unspecified"))
      (node (ref "LED138") (pin "1") (pinfunction "DIN_1") (pintype "unspecified"))
    )
    (net (code "160") (name "Net-(LED138-DO)") (class "Default")
      (node (ref "LED138") (pin "3") (pinfunction "DO_3") (pintype "unspecified"))
      (node (ref "LED139") (pin "1") (pinfunction "DIN_1") (pintype "unspecified"))
    )
    (net (code "161") (name "Net-(LED139-DO)") (class "Default")
      (node (ref "LED139") (pin "3") (pinfunction "DO_3") (pintype "unspecified"))
      (node (ref "LED140") (pin "1") (pinfunction "DIN_1") (pintype "unspecified"))
    )
    (net (code "162") (name "Net-(LED140-DO)") (class "Default")
      (node (ref "LED140") (pin "3") (pinfunction "DO_3") (pintype "unspecified"))
      (node (ref "LED141") (pin "1") (pinfunction "DIN_1") (pintype "unspecified"))
    )
    (net (code "163") (name "Net-(LED141-DO)") (class "Default")
      (node (ref "LED141") (pin "3") (pinfunction "DO_3") (pintype "unspecified"))
      (node (ref "LED142") (pin "1") (pinfunction "DIN_1") (pintype "unspecified"))
    )
    (net (code "164") (name "Net-(LED142-DO)") (class "Default")
      (node (ref "LED142") (pin "3") (pinfunction "DO_3") (pintype "unspecified"))
      (node (ref "LED143") (pin "1") (pinfunction "DIN_1") (pintype "unspecified"))
    )
    (net (code "165") (name "Net-(LED143-DO)") (class "Default")
      (node (ref "LED143") (pin "3") (pinfunction "DO_3") (pintype "unspecified"))
      (node (ref "LED144") (pin "1") (pinfunction "DIN_1") (pintype "unspecified"))
    )
    (net (code "166") (name "Net-(LED144-DO)") (class "Default")
      (node (ref "LED144") (pin "3") (pinfunction "DO_3") (pintype "unspecified"))
      (node (ref "LED145") (pin "1") (pinfunction "DIN_1") (pintype "unspecified"))
    )
    (net (code "167") (name "Net-(LED145-DO)") (class "Default")
      (node (ref "LED145") (pin "3") (pinfunction "DO_3") (pintype "unspecified"))
      (node (ref "LED146") (pin "1") (pinfunction "DIN_1") (pintype "unspecified"))
    )
    (net (code "168") (name "Net-(LED146-DO)") (class "Default")
      (node (ref "LED146") (pin "3") (pinfunction "DO_3") (pintype "unspecified"))
      (node (ref "LED147") (pin "1") (pinfunction "DIN_1") (pintype "unspecified"))
    )
    (net (code "169") (name "Net-(LED147-DO)") (class "Default")
      (node (ref "LED147") (pin "3") (pinfunction "DO_3") (pintype "unspecified"))
      (node (ref "LED148") (pin "1") (pinfunction "DIN_1") (pintype "unspecified"))
    )
    (net (code "170") (name "Net-(LED148-DO)") (class "Default")
      (node (ref "LED148") (pin "3") (pinfunction "DO_3") (pintype "unspecified"))
      (node (ref "LED149") (pin "1") (pinfunction "DIN_1") (pintype "unspecified"))
    )
    (net (code "171") (name "Net-(LED149-DO)") (class "Default")
      (node (ref "LED149") (pin "3") (pinfunction "DO_3") (pintype "unspecified"))
      (node (ref "LED150") (pin "1") (pinfunction "DIN_1") (pintype "unspecified"))
    )
    (net (code "172") (name "Net-(LED150-DO)") (class "Default")
      (node (ref "LED150") (pin "3") (pinfunction "DO_3") (pintype "unspecified"))
      (node (ref "LED151") (pin "1") (pinfunction "DIN_1") (pintype "unspecified"))
    )
    (net (code "173") (name "Net-(LED151-DO)") (class "Default")
      (node (ref "LED151") (pin "3") (pinfunction "DO_3") (pintype "unspecified"))
      (node (ref "LED152") (pin "1") (pinfunction "DIN_1") (pintype "unspecified"))
    )
    (net (code "174") (name "Net-(LED152-DO)") (class "Default")
      (node (ref "LED152") (pin "3") (pinfunction "DO_3") (pintype "unspecified"))
      (node (ref "LED153") (pin "1") (pinfunction "DIN_1") (pintype "unspecified"))
    )
    (net (code "175") (name "Net-(LED153-DO)") (class "Default")
      (node (ref "LED153") (pin "3") (pinfunction "DO_3") (pintype "unspecified"))
      (node (ref "LED154") (pin "1") (pinfunction "DIN_1") (pintype "unspecified"))
    )
    (net (code "176") (name "Net-(LED154-DO)") (class "Default")
      (node (ref "LED154") (pin "3") (pinfunction "DO_3") (pintype "unspecified"))
      (node (ref "LED155") (pin "1") (pinfunction "DIN_1") (pintype "unspecified"))
    )
    (net (code "177") (name "Net-(LED155-DO)") (class "Default")
      (node (ref "LED155") (pin "3") (pinfunction "DO_3") (pintype "unspecified"))
      (node (ref "LED156") (pin "1") (pinfunction "DIN_1") (pintype "unspecified"))
    )
    (net (code "178") (name "Net-(LED156-DO)") (class "Default")
      (node (ref "LED156") (pin "3") (pinfunction "DO_3") (pintype "unspecified"))
      (node (ref "LED157") (pin "1") (pinfunction "DIN_1") (pintype "unspecified"))
    )
    (net (code "179") (name "Net-(LED157-DO)") (class "Default")
      (node (ref "LED157") (pin "3") (pinfunction "DO_3") (pintype "unspecified"))
      (node (ref "LED158") (pin "1") (pinfunction "DIN_1") (pintype "unspecified"))
    )
    (net (code "180") (name "Net-(LED158-DO)") (class "Default")
      (node (ref "LED158") (pin "3") (pinfunction "DO_3") (pintype "unspecified"))
      (node (ref "LED159") (pin "1") (pinfunction "DIN_1") (pintype "unspecified"))
    )
    (net (code "181") (name "Net-(LED159-DO)") (class "Default")
      (node (ref "LED159") (pin "3") (pinfunction "DO_3") (pintype "unspecified"))
      (node (ref "LED160") (pin "1") (pinfunction "DIN_1") (pintype "unspecified"))
    )
    (net (code "182") (name "Net-(LED160-DO)") (class "Default")
      (node (ref "LED160") (pin "3") (pinfunction "DO_3") (pintype "unspecified"))
      (node (ref "LED161") (pin "1") (pinfunction "DIN_1") (pintype "unspecified"))
    )
    (net (code "183") (name "Net-(LED161-DO)") (class "Default")
      (node (ref "LED161") (pin "3") (pinfunction "DO_3") (pintype "unspecified"))
      (node (ref "LED162") (pin "1") (pinfunction "DIN_1") (pintype "unspecified"))
    )
    (net (code "184") (name "Net-(LED162-DO)") (class "Default")
      (node (ref "LED162") (pin "3") (pinfunction "DO_3") (pintype "unspecified"))
      (node (ref "LED163") (pin "1") (pinfunction "DIN_1") (pintype "unspecified"))
    )
    (net (code "185") (name "Net-(LED163-DO)") (class "Default")
      (node (ref "LED163") (pin "3") (pinfunction "DO_3") (pintype "unspecified"))
      (node (ref "LED164") (pin "1") (pinfunction "DIN_1") (pintype "unspecified"))
    )
    (net (code "186") (name "Net-(LED164-DO)") (class "Default")
      (node (ref "LED164") (pin "3") (pinfunction "DO_3") (pintype "unspecified"))
      (node (ref "LED165") (pin "1") (pinfunction "DIN_1") (pintype "unspecified"))
    )
    (net (code "187") (name "Net-(LED165-DO)") (class "Default")
      (node (ref "LED165") (pin "3") (pinfunction "DO_3") (pintype "unspecified"))
      (node (ref "LED166") (pin "1") (pinfunction "DIN_1") (pintype "unspecified"))
    )
    (net (code "188") (name "Net-(LED166-DO)") (class "Default")
      (node (ref "LED166") (pin "3") (pinfunction "DO_3") (pintype "unspecified"))
      (node (ref "LED167") (pin "1") (pinfunction "DIN_1") (pintype "unspecified"))
    )
    (net (code "189") (name "Net-(LED167-DO)") (class "Default")
      (node (ref "LED167") (pin "3") (pinfunction "DO_3") (pintype "unspecified"))
      (node (ref "LED168") (pin "1") (pinfunction "DIN_1") (pintype "unspecified"))
    )
    (net (code "190") (name "Net-(LED168-DO)") (class "Default")
      (node (ref "LED168") (pin "3") (pinfunction "DO_3") (pintype "unspecified"))
      (node (ref "LED169") (pin "1") (pinfunction "DIN_1") (pintype "unspecified"))
    )
    (net (code "191") (name "Net-(LED169-DO)") (class "Default")
      (node (ref "LED169") (pin "3") (pinfunction "DO_3") (pintype "unspecified"))
      (node (ref "LED170") (pin "1") (pinfunction "DIN_1") (pintype "unspecified"))
    )
    (net (code "192") (name "Net-(LED170-DO)") (class "Default")
      (node (ref "LED170") (pin "3") (pinfunction "DO_3") (pintype "unspecified"))
      (node (ref "LED171") (pin "1") (pinfunction "DIN_1") (pintype "unspecified"))
    )
    (net (code "193") (name "Net-(LED171-DO)") (class "Default")
      (node (ref "LED171") (pin "3") (pinfunction "DO_3") (pintype "unspecified"))
      (node (ref "LED172") (pin "1") (pinfunction "DIN_1") (pintype "unspecified"))
    )
    (net (code "194") (name "Net-(LED172-DO)") (class "Default")
      (node (ref "LED172") (pin "3") (pinfunction "DO_3") (pintype "unspecified"))
      (node (ref "LED173") (pin "1") (pinfunction "DIN_1") (pintype "unspecified"))
    )
    (net (code "195") (name "Net-(LED173-DO)") (class "Default")
      (node (ref "LED173") (pin "3") (pinfunction "DO_3") (pintype "unspecified"))
      (node (ref "LED174") (pin "1") (pinfunction "DIN_1") (pintype "unspecified"))
    )
    (net (code "196") (name "Net-(LED174-DO)") (class "Default")
      (node (ref "LED174") (pin "3") (pinfunction "DO_3") (pintype "unspecified"))
      (node (ref "LED175") (pin "1") (pinfunction "DIN_1") (pintype "unspecified"))
    )
    (net (code "197") (name "Net-(LED175-DO)") (class "Default")
      (node (ref "LED175") (pin "3") (pinfunction "DO_3") (pintype "unspecified"))
      (node (ref "LED176") (pin "1") (pinfunction "DIN_1") (pintype "unspecified"))
    )
    (net (code "198") (name "Net-(LED176-DO)") (class "Default")
      (node (ref "LED176") (pin "3") (pinfunction "DO_3") (pintype "unspecified"))
      (node (ref "LED177") (pin "1") (pinfunction "DIN_1") (pintype "unspecified"))
    )
    (net (code "199") (name "Net-(LED177-DO)") (class "Default")
      (node (ref "LED177") (pin "3") (pinfunction "DO_3") (pintype "unspecified"))
      (node (ref "LED178") (pin "1") (pinfunction "DIN_1") (pintype "unspecified"))
    )
    (net (code "200") (name "Net-(LED178-DO)") (class "Default")
      (node (ref "LED178") (pin "3") (pinfunction "DO_3") (pintype "unspecified"))
      (node (ref "LED179") (pin "1") (pinfunction "DIN_1") (pintype "unspecified"))
    )
    (net (code "201") (name "Net-(LED179-DO)") (class "Default")
      (node (ref "LED179") (pin "3") (pinfunction "DO_3") (pintype "unspecified"))
      (node (ref "LED180") (pin "1") (pinfunction "DIN_1") (pintype "unspecified"))
    )
    (net (code "202") (name "Net-(LED180-DO)") (class "Default")
      (node (ref "LED180") (pin "3") (pinfunction "DO_3") (pintype "unspecified"))
      (node (ref "LED181") (pin "1") (pinfunction "DIN_1") (pintype "unspecified"))
    )
    (net (code "203") (name "Net-(LED181-DO)") (class "Default")
      (node (ref "LED181") (pin "3") (pinfunction "DO_3") (pintype "unspecified"))
      (node (ref "LED182") (pin "1") (pinfunction "DIN_1") (pintype "unspecified"))
    )
    (net (code "204") (name "Net-(LED182-DO)") (class "Default")
      (node (ref "LED182") (pin "3") (pinfunction "DO_3") (pintype "unspecified"))
      (node (ref "LED183") (pin "1") (pinfunction "DIN_1") (pintype "unspecified"))
    )
    (net (code "205") (name "Net-(LED183-DO)") (class "Default")
      (node (ref "LED183") (pin "3") (pinfunction "DO_3") (pintype "unspecified"))
      (node (ref "LED184") (pin "1") (pinfunction "DIN_1") (pintype "unspecified"))
    )
    (net (code "206") (name "Net-(LED184-DO)") (class "Default")
      (node (ref "LED184") (pin "3") (pinfunction "DO_3") (pintype "unspecified"))
      (node (ref "LED185") (pin "1") (pinfunction "DIN_1") (pintype "unspecified"))
    )
    (net (code "207") (name "Net-(LED185-DO)") (class "Default")
      (node (ref "LED185") (pin "3") (pinfunction "DO_3") (pintype "unspecified"))
      (node (ref "LED186") (pin "1") (pinfunction "DIN_1") (pintype "unspecified"))
    )
    (net (code "208") (name "Net-(LED186-DO)") (class "Default")
      (node (ref "LED186") (pin "3") (pinfunction "DO_3") (pintype "unspecified"))
      (node (ref "LED187") (pin "1") (pinfunction "DIN_1") (pintype "unspecified"))
    )
    (net (code "209") (name "Net-(LED188-DO)") (class "Default")
      (node (ref "LED188") (pin "3") (pinfunction "DO_3") (pintype "unspecified"))
      (node (ref "LED189") (pin "1") (pinfunction "DIN_1") (pintype "unspecified"))
    )
    (net (code "210") (name "Net-(LED189-DO)") (class "Default")
      (node (ref "LED189") (pin "3") (pinfunction "DO_3") (pintype "unspecified"))
      (node (ref "LED190") (pin "1") (pinfunction "DIN_1") (pintype "unspecified"))
    )
    (net (code "211") (name "Net-(LED190-DO)") (class "Default")
      (node (ref "LED190") (pin "3") (pinfunction "DO_3") (pintype "unspecified"))
      (node (ref "LED191") (pin "1") (pinfunction "DIN_1") (pintype "unspecified"))
    )
    (net (code "212") (name "Net-(LED191-DO)") (class "Default")
      (node (ref "LED191") (pin "3") (pinfunction "DO_3") (pintype "unspecified"))
      (node (ref "LED192") (pin "1") (pinfunction "DIN_1") (pintype "unspecified"))
    )
    (net (code "213") (name "Net-(LED192-DO)") (class "Default")
      (node (ref "LED192") (pin "3") (pinfunction "DO_3") (pintype "unspecified"))
      (node (ref "LED193") (pin "1") (pinfunction "DIN_1") (pintype "unspecified"))
    )
    (net (code "214") (name "Net-(LED193-DO)") (class "Default")
      (node (ref "LED193") (pin "3") (pinfunction "DO_3") (pintype "unspecified"))
      (node (ref "LED194") (pin "1") (pinfunction "DIN_1") (pintype "unspecified"))
    )
    (net (code "215") (name "Net-(LED194-DO)") (class "Default")
      (node (ref "LED194") (pin "3") (pinfunction "DO_3") (pintype "unspecified"))
      (node (ref "LED195") (pin "1") (pinfunction "DIN_1") (pintype "unspecified"))
    )
    (net (code "216") (name "Net-(LED195-DO)") (class "Default")
      (node (ref "LED195") (pin "3") (pinfunction "DO_3") (pintype "unspecified"))
      (node (ref "LED196") (pin "1") (pinfunction "DIN_1") (pintype "unspecified"))
    )
    (net (code "217") (name "Net-(LED196-DO)") (class "Default")
      (node (ref "LED196") (pin "3") (pinfunction "DO_3") (pintype "unspecified"))
      (node (ref "LED197") (pin "1") (pinfunction "DIN_1") (pintype "unspecified"))
    )
    (net (code "218") (name "Net-(LED197-DO)") (class "Default")
      (node (ref "LED197") (pin "3") (pinfunction "DO_3") (pintype "unspecified"))
      (node (ref "LED198") (pin "1") (pinfunction "DIN_1") (pintype "unspecified"))
    )
    (net (code "219") (name "Net-(LED198-DO)") (class "Default")
      (node (ref "LED198") (pin "3") (pinfunction "DO_3") (pintype "unspecified"))
      (node (ref "LED199") (pin "1") (pinfunction "DIN_1") (pintype "unspecified"))
    )
    (net (code "220") (name "Net-(LED199-DO)") (class "Default")
      (node (ref "LED199") (pin "3") (pinfunction "DO_3") (pintype "unspecified"))
      (node (ref "LED200") (pin "1") (pinfunction "DIN_1") (pintype "unspecified"))
    )
    (net (code "221") (name "Net-(LED200-DO)") (class "Default")
      (node (ref "LED200") (pin "3") (pinfunction "DO_3") (pintype "unspecified"))
      (node (ref "LED201") (pin "1") (pinfunction "DIN_1") (pintype "unspecified"))
    )
    (net (code "222") (name "Net-(LED201-DO)") (class "Default")
      (node (ref "LED201") (pin "3") (pinfunction "DO_3") (pintype "unspecified"))
      (node (ref "LED202") (pin "1") (pinfunction "DIN_1") (pintype "unspecified"))
    )
    (net (code "223") (name "Net-(LED202-DO)") (class "Default")
      (node (ref "LED202") (pin "3") (pinfunction "DO_3") (pintype "unspecified"))
      (node (ref "LED203") (pin "1") (pinfunction "DIN_1") (pintype "unspecified"))
    )
    (net (code "224") (name "Net-(LED203-DO)") (class "Default")
      (node (ref "LED203") (pin "3") (pinfunction "DO_3") (pintype "unspecified"))
      (node (ref "LED204") (pin "1") (pinfunction "DIN_1") (pintype "unspecified"))
    )
    (net (code "225") (name "Net-(LED204-DO)") (class "Default")
      (node (ref "LED204") (pin "3") (pinfunction "DO_3") (pintype "unspecified"))
      (node (ref "LED205") (pin "1") (pinfunction "DIN_1") (pintype "unspecified"))
    )
    (net (code "226") (name "Net-(LED205-DO)") (class "Default")
      (node (ref "LED205") (pin "3") (pinfunction "DO_3") (pintype "unspecified"))
      (node (ref "LED206") (pin "1") (pinfunction "DIN_1") (pintype "unspecified"))
    )
    (net (code "227") (name "Net-(LED206-DO)") (class "Default")
      (node (ref "LED206") (pin "3") (pinfunction "DO_3") (pintype "unspecified"))
      (node (ref "LED207") (pin "1") (pinfunction "DIN_1") (pintype "unspecified"))
    )
    (net (code "228") (name "Net-(LED207-DO)") (class "Default")
      (node (ref "LED207") (pin "3") (pinfunction "DO_3") (pintype "unspecified"))
      (node (ref "LED208") (pin "1") (pinfunction "DIN_1") (pintype "unspecified"))
    )
    (net (code "229") (name "Net-(LED208-DO)") (class "Default")
      (node (ref "LED208") (pin "3") (pinfunction "DO_3") (pintype "unspecified"))
      (node (ref "LED209") (pin "1") (pinfunction "DIN_1") (pintype "unspecified"))
    )
    (net (code "230") (name "Net-(LED209-DO)") (class "Default")
      (node (ref "LED209") (pin "3") (pinfunction "DO_3") (pintype "unspecified"))
      (node (ref "LED210") (pin "1") (pinfunction "DIN_1") (pintype "unspecified"))
    )
    (net (code "231") (name "Net-(LED210-DO)") (class "Default")
      (node (ref "LED210") (pin "3") (pinfunction "DO_3") (pintype "unspecified"))
      (node (ref "LED211") (pin "1") (pinfunction "DIN_1") (pintype "unspecified"))
    )
    (net (code "232") (name "Net-(LED211-DO)") (class "Default")
      (node (ref "LED211") (pin "3") (pinfunction "DO_3") (pintype "unspecified"))
      (node (ref "LED212") (pin "1") (pinfunction "DIN_1") (pintype "unspecified"))
    )
    (net (code "233") (name "Net-(LED212-DO)") (class "Default")
      (node (ref "LED212") (pin "3") (pinfunction "DO_3") (pintype "unspecified"))
      (node (ref "LED213") (pin "1") (pinfunction "DIN_1") (pintype "unspecified"))
    )
    (net (code "234") (name "Net-(LED213-DO)") (class "Default")
      (node (ref "LED213") (pin "3") (pinfunction "DO_3") (pintype "unspecified"))
      (node (ref "LED214") (pin "1") (pinfunction "DIN_1") (pintype "unspecified"))
    )
    (net (code "235") (name "Net-(LED214-DO)") (class "Default")
      (node (ref "LED214") (pin "3") (pinfunction "DO_3") (pintype "unspecified"))
      (node (ref "LED215") (pin "1") (pinfunction "DIN_1") (pintype "unspecified"))
    )
    (net (code "236") (name "Net-(LED215-DO)") (class "Default")
      (node (ref "LED215") (pin "3") (pinfunction "DO_3") (pintype "unspecified"))
      (node (ref "LED216") (pin "1") (pinfunction "DIN_1") (pintype "unspecified"))
    )
    (net (code "237") (name "Net-(LED216-DO)") (class "Default")
      (node (ref "LED216") (pin "3") (pinfunction "DO_3") (pintype "unspecified"))
      (node (ref "LED217") (pin "1") (pinfunction "DIN_1") (pintype "unspecified"))
    )
    (net (code "238") (name "Net-(LED217-DO)") (class "Default")
      (node (ref "LED217") (pin "3") (pinfunction "DO_3") (pintype "unspecified"))
      (node (ref "LED218") (pin "1") (pinfunction "DIN_1") (pintype "unspecified"))
    )
    (net (code "239") (name "Net-(LED218-DO)") (class "Default")
      (node (ref "LED218") (pin "3") (pinfunction "DO_3") (pintype "unspecified"))
      (node (ref "LED219") (pin "1") (pinfunction "DIN_1") (pintype "unspecified"))
    )
    (net (code "240") (name "Net-(LED219-DO)") (class "Default")
      (node (ref "LED219") (pin "3") (pinfunction "DO_3") (pintype "unspecified"))
      (node (ref "LED220") (pin "1") (pinfunction "DIN_1") (pintype "unspecified"))
    )
    (net (code "241") (name "Net-(LED220-DO)") (class "Default")
      (node (ref "LED220") (pin "3") (pinfunction "DO_3") (pintype "unspecified"))
      (node (ref "LED221") (pin "1") (pinfunction "DIN_1") (pintype "unspecified"))
    )
    (net (code "242") (name "Net-(LED221-DO)") (class "Default")
      (node (ref "LED221") (pin "3") (pinfunction "DO_3") (pintype "unspecified"))
      (node (ref "LED222") (pin "1") (pinfunction "DIN_1") (pintype "unspecified"))
    )
    (net (code "243") (name "Net-(LED222-DO)") (class "Default")
      (node (ref "LED222") (pin "3") (pinfunction "DO_3") (pintype "unspecified"))
      (node (ref "LED223") (pin "1") (pinfunction "DIN_1") (pintype "unspecified"))
    )
    (net (code "244") (name "Net-(U1-Y)") (class "Default")
      (node (ref "R4") (pin "1") (pinfunction "1_1") (pintype "input"))
      (node (ref "U1") (pin "4") (pinfunction "Y_4") (pintype "unspecified"))
    )
    (net (code "245") (name "Net-(U2-OSCI)") (class "Default")
      (node (ref "C11") (pin "1") (pinfunction "1_1") (pintype "input"))
      (node (ref "U2") (pin "1") (pinfunction "OSCI_1") (pintype "unspecified"))
      (node (ref "X1") (pin "2") (pinfunction "2_2") (pintype "unspecified"))
    )
    (net (code "246") (name "Net-(U2-OSCO)") (class "Default")
      (node (ref "U2") (pin "2") (pinfunction "OSCO_2") (pintype "unspecified"))
      (node (ref "X1") (pin "1") (pinfunction "1_1") (pintype "unspecified"))
    )
    (net (code "247") (name "Net-(U4-TXD0)") (class "Default")
      (node (ref "R3") (pin "1") (pinfunction "1_1") (pintype "input"))
      (node (ref "U4") (pin "31") (pinfunction "TXD0_31") (pintype "unspecified"))
    )
    (net (code "248") (name "Net-(USBC1-CC1)") (class "Default")
      (node (ref "R10") (pin "1") (pinfunction "1_1") (pintype "input"))
      (node (ref "USBC1") (pin "A5") (pinfunction "CC1_A5") (pintype "unspecified"))
    )
    (net (code "249") (name "Net-(USBC1-CC2)") (class "Default")
      (node (ref "R9") (pin "2") (pinfunction "2_2") (pintype "input"))
      (node (ref "USBC1") (pin "B5") (pinfunction "CC2_B5") (pintype "unspecified"))
    )
    (net (code "250") (name "VBUS") (class "Default")
      (node (ref "D3") (pin "1") (pinfunction "1_1") (pintype "unspecified"))
      (node (ref "D4") (pin "2") (pinfunction "+_2") (pintype "unspecified"))
      (node (ref "USBC1") (pin "A4") (pinfunction "VBUS_A4") (pintype "unspecified"))
      (node (ref "USBC1") (pin "A9") (pinfunction "VBUS_A9") (pintype "unspecified"))
    )
    (net (code "251") (name "unconnected-(CN1-Pad0)") (class "Default")
      (node (ref "CN1") (pin "0") (pinfunction "0_0") (pintype "unspecified+no_connect"))
    )
    (net (code "252") (name "unconnected-(CN1-Pad0)_1") (class "Default")
      (node (ref "CN1") (pin "0") (pinfunction "0_0") (pintype "unspecified+no_connect"))
    )
    (net (code "253") (name "unconnected-(JOY1-Pad7)") (class "Default")
      (node (ref "JOY1") (pin "7") (pinfunction "7_7") (pintype "unspecified+no_connect"))
    )
    (net (code "254") (name "unconnected-(JOY1-Pad8)") (class "Default")
      (node (ref "JOY1") (pin "8") (pinfunction "8_8") (pintype "unspecified+no_connect"))
    )
    (net (code "255") (name "unconnected-(LED223-DO-Pad3)") (class "Default")
      (node (ref "LED223") (pin "3") (pinfunction "DO_3") (pintype "unspecified+no_connect"))
    )
    (net (code "256") (name "unconnected-(U1-NC-Pad1)") (class "Default")
      (node (ref "U1") (pin "1") (pinfunction "NC_1") (pintype "unspecified+no_connect"))
    )
    (net (code "257") (name "unconnected-(U2-CLKOUT-Pad7)") (class "Default")
      (node (ref "U2") (pin "7") (pinfunction "CLKOUT_7") (pintype "unspecified+no_connect"))
    )
    (net (code "258") (name "unconnected-(U3-Vout-Pad4)") (class "Default")
      (node (ref "U3") (pin "4") (pinfunction "Vout_4") (pintype "unspecified+no_connect"))
    )
    (net (code "259") (name "unconnected-(U4-NC-Pad4)") (class "Default")
      (node (ref "U4") (pin "4") (pinfunction "NC_4") (pintype "unspecified+no_connect"))
    )
    (net (code "260") (name "unconnected-(U4-NC-Pad7)") (class "Default")
      (node (ref "U4") (pin "7") (pinfunction "NC_7") (pintype "unspecified+no_connect"))
    )
    (net (code "261") (name "unconnected-(U4-NC-Pad9)") (class "Default")
      (node (ref "U4") (pin "9") (pinfunction "NC_9") (pintype "unspecified+no_connect"))
    )
    (net (code "262") (name "unconnected-(U4-NC-Pad10)") (class "Default")
      (node (ref "U4") (pin "10") (pinfunction "NC_10") (pintype "unspecified+no_connect"))
    )
    (net (code "263") (name "unconnected-(U4-NC-Pad15)") (class "Default")
      (node (ref "U4") (pin "15") (pinfunction "NC_15") (pintype "unspecified+no_connect"))
    )
    (net (code "264") (name "unconnected-(U4-NC-Pad17)") (class "Default")
      (node (ref "U4") (pin "17") (pinfunction "NC_17") (pintype "unspecified+no_connect"))
    )
    (net (code "265") (name "unconnected-(U4-NC-Pad24)") (class "Default")
      (node (ref "U4") (pin "24") (pinfunction "NC_24") (pintype "unspecified+no_connect"))
    )
    (net (code "266") (name "unconnected-(U4-NC-Pad25)") (class "Default")
      (node (ref "U4") (pin "25") (pinfunction "NC_25") (pintype "unspecified+no_connect"))
    )
    (net (code "267") (name "unconnected-(U4-NC-Pad28)") (class "Default")
      (node (ref "U4") (pin "28") (pinfunction "NC_28") (pintype "unspecified+no_connect"))
    )
    (net (code "268") (name "unconnected-(U4-NC-Pad29)") (class "Default")
      (node (ref "U4") (pin "29") (pinfunction "NC_29") (pintype "unspecified+no_connect"))
    )
    (net (code "269") (name "unconnected-(U4-NC-Pad32)") (class "Default")
      (node (ref "U4") (pin "32") (pinfunction "NC_32") (pintype "unspecified+no_connect"))
    )
    (net (code "270") (name "unconnected-(U4-NC-Pad33)") (class "Default")
      (node (ref "U4") (pin "33") (pinfunction "NC_33") (pintype "unspecified+no_connect"))
    )
    (net (code "271") (name "unconnected-(U4-NC-Pad34)") (class "Default")
      (node (ref "U4") (pin "34") (pinfunction "NC_34") (pintype "unspecified+no_connect"))
    )
    (net (code "272") (name "unconnected-(U4-NC-Pad35)") (class "Default")
      (node (ref "U4") (pin "35") (pinfunction "NC_35") (pintype "unspecified+no_connect"))
    )
    (net (code "273") (name "unconnected-(USBC1-Pad0)") (class "Default")
      (node (ref "USBC1") (pin "0") (pinfunction "0_0") (pintype "unspecified+no_connect"))
    )
    (net (code "274") (name "unconnected-(USBC1-Pad0)_1") (class "Default")
      (node (ref "USBC1") (pin "0") (pinfunction "0_0") (pintype "unspecified+no_connect"))
    )
    (net (code "275") (name "unconnected-(USBC1-Pad0)_2") (class "Default")
      (node (ref "USBC1") (pin "0") (pinfunction "0_0") (pintype "unspecified+no_connect"))
    )
    (net (code "276") (name "unconnected-(USBC1-Pad0)_3") (class "Default")
      (node (ref "USBC1") (pin "0") (pinfunction "0_0") (pintype "unspecified+no_connect"))
    )
    (net (code "277") (name "unconnected-(USBC1-SBU1-PadA8)") (class "Default")
      (node (ref "USBC1") (pin "A8") (pinfunction "SBU1_A8") (pintype "unspecified+no_connect"))
    )
    (net (code "278") (name "unconnected-(USBC1-SBU2-PadB8)") (class "Default")
      (node (ref "USBC1") (pin "B8") (pinfunction "SBU2_B8") (pintype "unspecified+no_connect"))
    )
  )
)
